# Main.net
KiCad netlist of a schematic drawn in Altium Designer
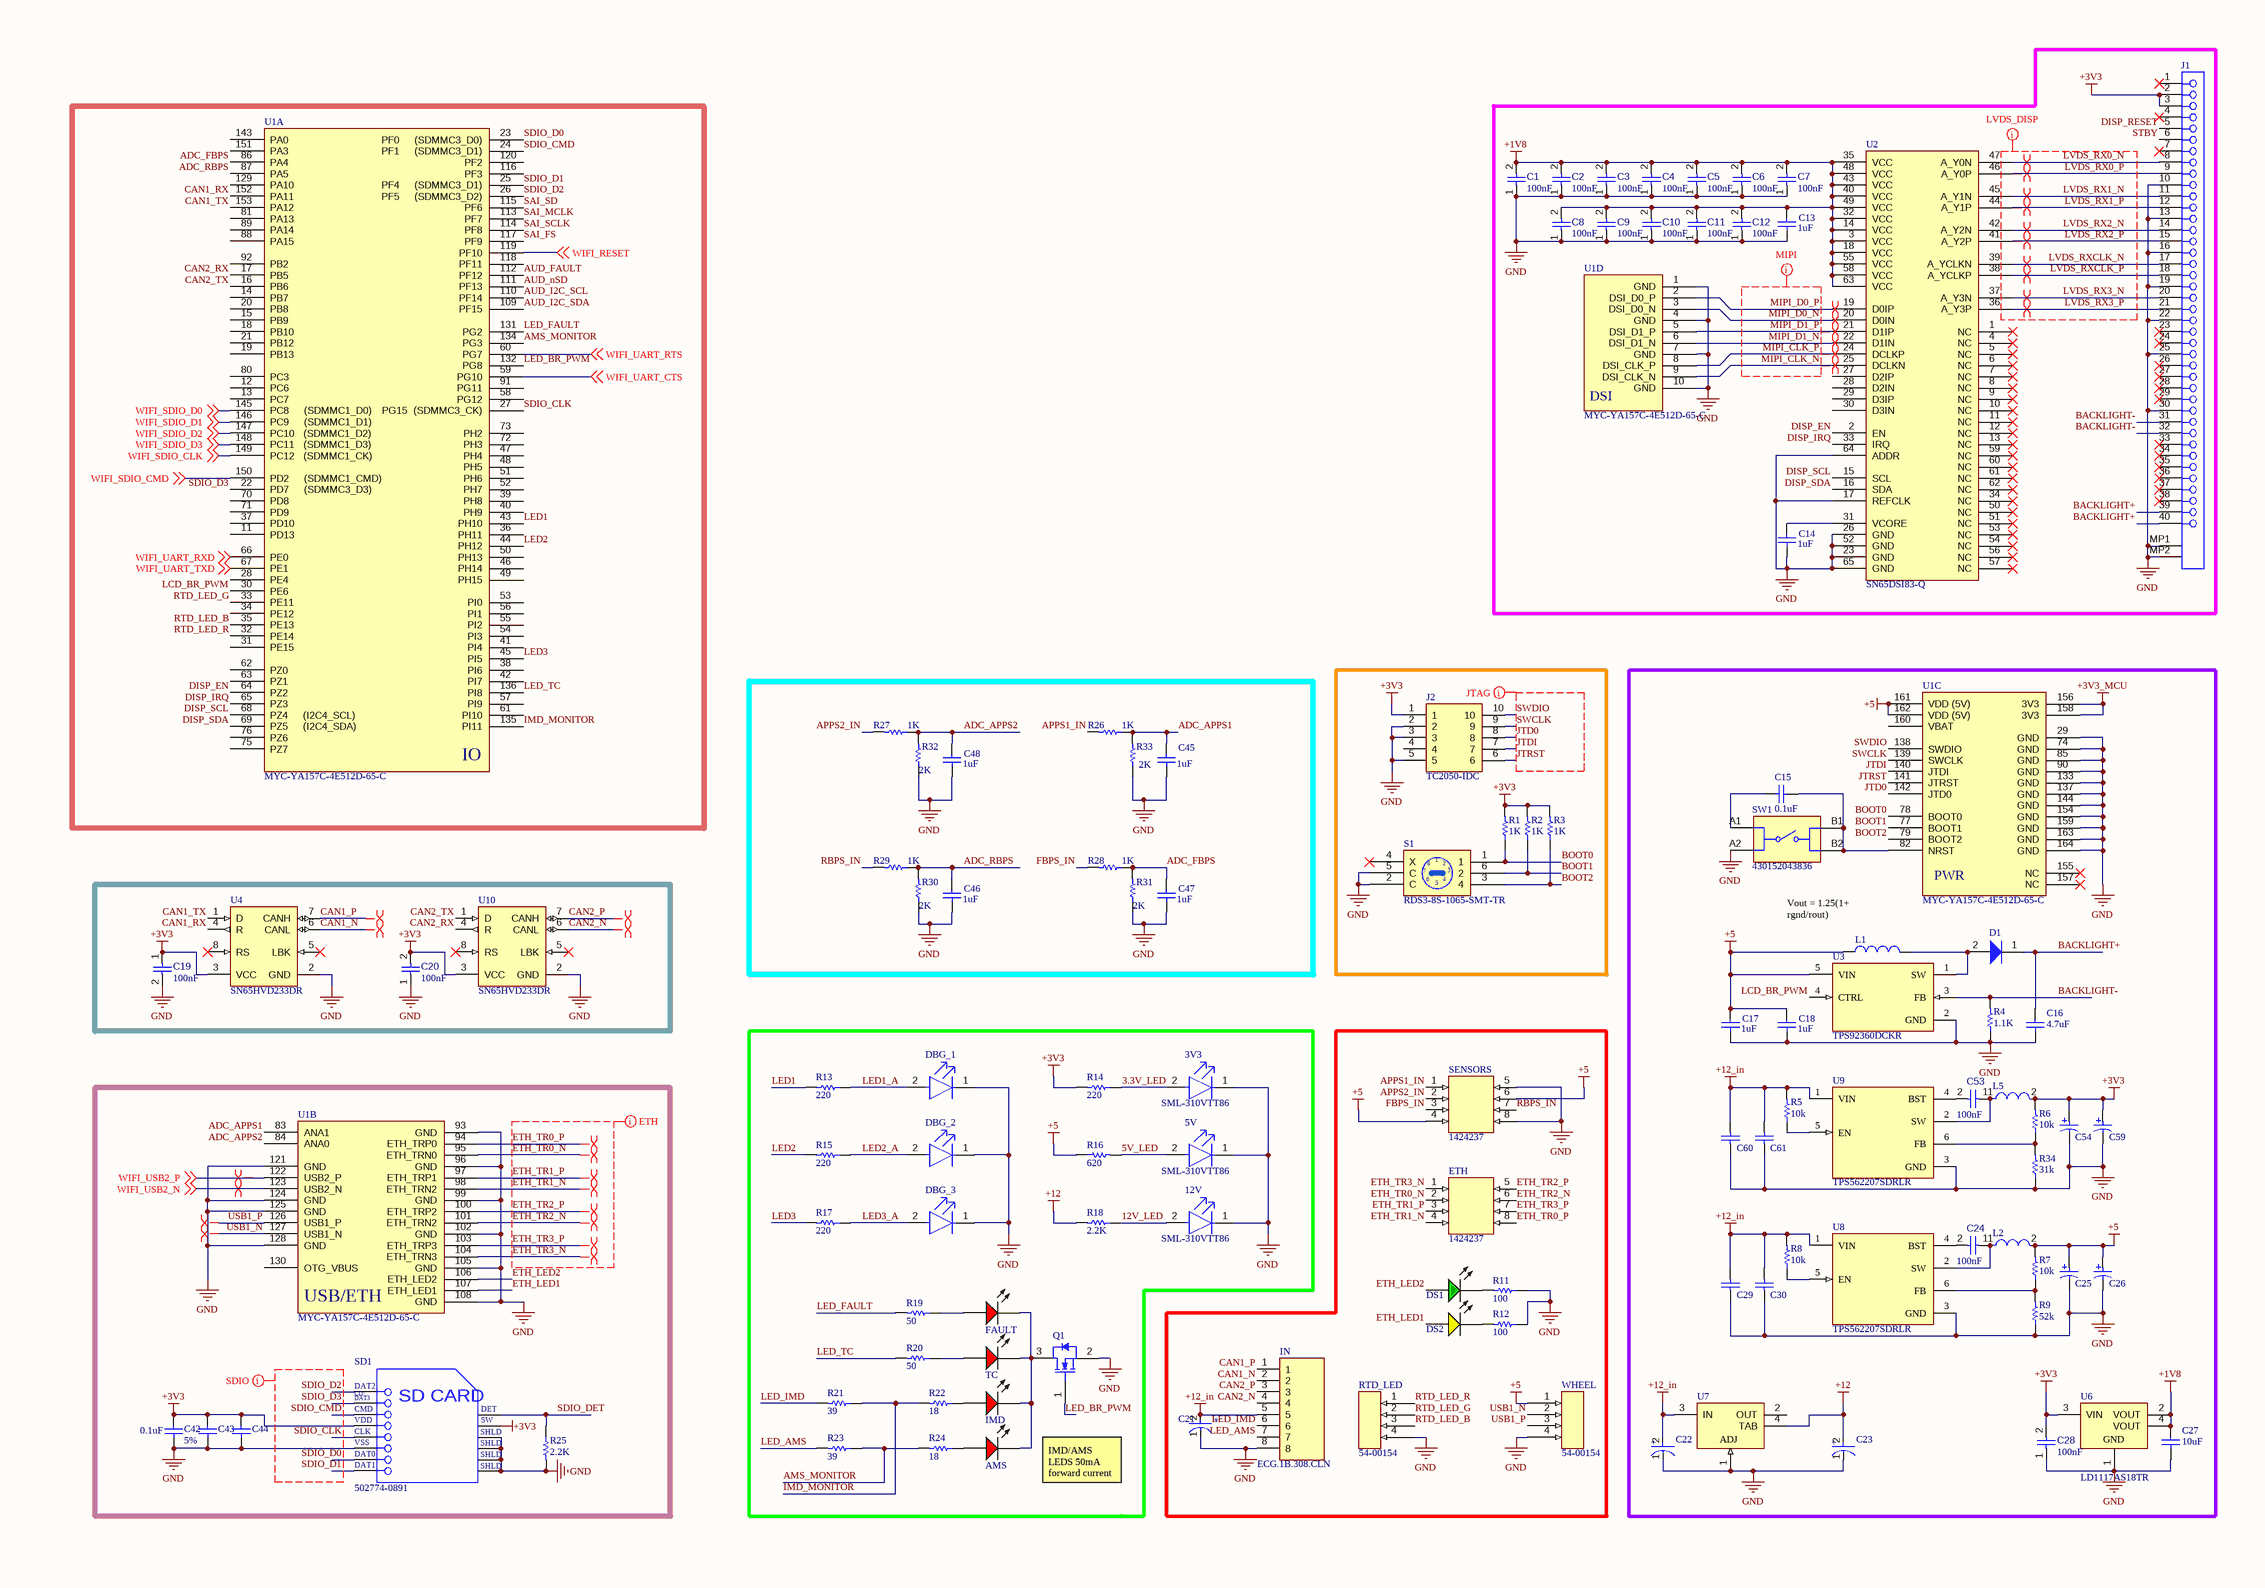
[diagram p0: Main.SchDoc]

(export (version "E")
  (design (tool "Eeschema 10.0.6"))
  (components
    (comp (ref "3V3")
      (value "SML-310VTT86")
      (footprint "FP-SML-310VTT86-MFG")
      (description "LED RED CLEAR 0603 SMD")
      (fields
        (field (name "OCTOPART") "https://octopart.com/sml-310vtt86-rohm-550741")
        (field (name "MANUFACTURER") "Rohm")
      )
      (libsource (lib "Altium Content Vault") (part "8706943c75ba83719d021d2fdc84c58"))
    )
    (comp (ref "5V")
      (value "SML-310VTT86")
      (footprint "FP-SML-310VTT86-MFG")
      (description "LED RED CLEAR 0603 SMD")
      (fields
        (field (name "OCTOPART") "https://octopart.com/sml-310vtt86-rohm-550741")
        (field (name "MANUFACTURER") "Rohm")
      )
      (libsource (lib "Altium Content Vault") (part "8706943c75ba83719d021d2fdc84c58"))
    )
    (comp (ref "12V")
      (value "SML-310VTT86")
      (footprint "FP-SML-310VTT86-MFG")
      (description "LED RED CLEAR 0603 SMD")
      (fields
        (field (name "OCTOPART") "https://octopart.com/sml-310vtt86-rohm-550741")
        (field (name "MANUFACTURER") "Rohm")
      )
      (libsource (lib "Altium Content Vault") (part "8706943c75ba83719d021d2fdc84c58"))
    )
    (comp (ref "AMS")
      (value "C503B-RAN-CY0B0AA2")
      (footprint "CREE-C503B-RAN")
      (description "Cree(R) 5-mm Red Round LED, 2.1 V, -40 to 100 degC, 2-Pin THD, RoHS, Ammo")
      (fields (field (name "MANUFACTURER") "Cree"))
      (libsource (lib "Altium Content Vault") (part "LED-RED-AK-2"))
    )
    (comp (ref "C1")
      (value "100nF")
      (footprint "CAPC0402(1005)60_L")
      (description "Chip Capacitor, 100nF +/-20%, 25V, 0402, Thickness 0.6 mm")
      (fields (field (name "TOLERANCE") "10%") (field (name "Comment") "Capacitor 100nF +/-20% 25V 0402"))
      (libsource (lib "Nicolespace") (part "CAP-NP-2"))
    )
    (comp (ref "C2")
      (value "100nF")
      (footprint "CAPC0402(1005)60_L")
      (description "Chip Capacitor, 100nF +/-20%, 25V, 0402, Thickness 0.6 mm")
      (fields (field (name "TOLERANCE") "10%") (field (name "Comment") "Capacitor 100nF +/-20% 25V 0402"))
      (libsource (lib "Nicolespace") (part "CAP-NP-2"))
    )
    (comp (ref "C3")
      (value "100nF")
      (footprint "CAPC0402(1005)60_L")
      (description "Chip Capacitor, 100nF +/-20%, 25V, 0402, Thickness 0.6 mm")
      (fields (field (name "TOLERANCE") "10%") (field (name "Comment") "Capacitor 100nF +/-20% 25V 0402"))
      (libsource (lib "Nicolespace") (part "CAP-NP-2"))
    )
    (comp (ref "C4")
      (value "100nF")
      (footprint "CAPC0402(1005)60_L")
      (description "Chip Capacitor, 100nF +/-20%, 25V, 0402, Thickness 0.6 mm")
      (fields (field (name "TOLERANCE") "10%") (field (name "Comment") "Capacitor 100nF +/-20% 25V 0402"))
      (libsource (lib "Nicolespace") (part "CAP-NP-2"))
    )
    (comp (ref "C5")
      (value "100nF")
      (footprint "CAPC0402(1005)60_L")
      (description "Chip Capacitor, 100nF +/-20%, 25V, 0402, Thickness 0.6 mm")
      (fields (field (name "TOLERANCE") "10%") (field (name "Comment") "Capacitor 100nF +/-20% 25V 0402"))
      (libsource (lib "Nicolespace") (part "CAP-NP-2"))
    )
    (comp (ref "C6")
      (value "100nF")
      (footprint "CAPC0402(1005)60_L")
      (description "Chip Capacitor, 100nF +/-20%, 25V, 0402, Thickness 0.6 mm")
      (fields (field (name "TOLERANCE") "10%") (field (name "Comment") "Capacitor 100nF +/-20% 25V 0402"))
      (libsource (lib "Nicolespace") (part "CAP-NP-2"))
    )
    (comp (ref "C7")
      (value "100nF")
      (footprint "CAPC0402(1005)60_L")
      (description "Chip Capacitor, 100nF +/-20%, 25V, 0402, Thickness 0.6 mm")
      (fields (field (name "TOLERANCE") "10%") (field (name "Comment") "Capacitor 100nF +/-20% 25V 0402"))
      (libsource (lib "Nicolespace") (part "CAP-NP-2"))
    )
    (comp (ref "C8")
      (value "100nF")
      (footprint "CAPC0402(1005)60_L")
      (description "Chip Capacitor, 100nF +/-20%, 25V, 0402, Thickness 0.6 mm")
      (fields (field (name "TOLERANCE") "10%") (field (name "Comment") "Capacitor 100nF +/-20% 25V 0402"))
      (libsource (lib "Nicolespace") (part "CAP-NP-2"))
    )
    (comp (ref "C9")
      (value "100nF")
      (footprint "CAPC0402(1005)60_L")
      (description "Chip Capacitor, 100nF +/-20%, 25V, 0402, Thickness 0.6 mm")
      (fields (field (name "TOLERANCE") "10%") (field (name "Comment") "Capacitor 100nF +/-20% 25V 0402"))
      (libsource (lib "Nicolespace") (part "CAP-NP-2"))
    )
    (comp (ref "C10")
      (value "100nF")
      (footprint "CAPC0402(1005)60_L")
      (description "Chip Capacitor, 100nF +/-20%, 25V, 0402, Thickness 0.6 mm")
      (fields (field (name "TOLERANCE") "10%") (field (name "Comment") "Capacitor 100nF +/-20% 25V 0402"))
      (libsource (lib "Nicolespace") (part "CAP-NP-2"))
    )
    (comp (ref "C11")
      (value "100nF")
      (footprint "CAPC0402(1005)60_L")
      (description "Chip Capacitor, 100nF +/-20%, 25V, 0402, Thickness 0.6 mm")
      (fields (field (name "TOLERANCE") "10%") (field (name "Comment") "Capacitor 100nF +/-20% 25V 0402"))
      (libsource (lib "Nicolespace") (part "CAP-NP-2"))
    )
    (comp (ref "C12")
      (value "100nF")
      (footprint "CAPC0402(1005)60_L")
      (description "Chip Capacitor, 100nF +/-20%, 25V, 0402, Thickness 0.6 mm")
      (fields (field (name "TOLERANCE") "10%") (field (name "Comment") "Capacitor 100nF +/-20% 25V 0402"))
      (libsource (lib "Nicolespace") (part "CAP-NP-2"))
    )
    (comp (ref "C13")
      (value "1uF")
      (footprint "1608[0603]")
      (description "Capacitor")
      (fields (field (name "Comment") "Cap"))
      (libsource (lib "WWU_RCL") (part "Capacitor"))
    )
    (comp (ref "C14")
      (value "1uF")
      (footprint "1608[0603]")
      (description "Capacitor")
      (fields (field (name "Comment") "Cap"))
      (libsource (lib "WWU_RCL") (part "Capacitor"))
    )
    (comp (ref "C15")
      (value "0.1uF")
      (footprint "1608[0603]")
      (description "Capacitor")
      (fields (field (name "Comment") "Cap"))
      (libsource (lib "WWU_RCL") (part "Capacitor"))
    )
    (comp (ref "C16")
      (value "4.7uF")
      (footprint "1608[0603]")
      (description "Capacitor")
      (fields (field (name "Comment") "Cap"))
      (libsource (lib "WWU_RCL") (part "Capacitor"))
    )
    (comp (ref "C17")
      (value "1uF")
      (footprint "1608[0603]")
      (description "Capacitor")
      (fields (field (name "Comment") "Cap"))
      (libsource (lib "WWU_RCL") (part "Capacitor"))
    )
    (comp (ref "C18")
      (value "1uF")
      (footprint "1608[0603]")
      (description "Capacitor")
      (fields (field (name "Comment") "Cap"))
      (libsource (lib "WWU_RCL") (part "Capacitor"))
    )
    (comp (ref "C19")
      (value "100nF")
      (footprint "CAPC0402(1005)60_L")
      (description "Chip Capacitor, 100nF +/-20%, 25V, 0402, Thickness 0.6 mm")
      (fields (field (name "TOLERANCE") "10%") (field (name "Comment") "Capacitor 100nF +/-20% 25V 0402"))
      (libsource (lib "Nicolespace") (part "CAP-NP-2"))
    )
    (comp (ref "C20")
      (value "100nF")
      (footprint "CAPC0402(1005)60_L")
      (description "Chip Capacitor, 100nF +/-20%, 25V, 0402, Thickness 0.6 mm")
      (fields (field (name "TOLERANCE") "10%") (field (name "Comment") "Capacitor 100nF +/-20% 25V 0402"))
      (libsource (lib "Nicolespace") (part "CAP-NP-2"))
    )
    (comp (ref "C21")
      (value "EEFCX0G181XR")
      (footprint "FP-SP-Cap-X-MFG")
      (description "Molded Aluminum Polymer Capacitor 180uF 20% 4V life 2000Hours SMD 2917")
      (libsource (lib "Altium Content Vault") (part "203bc49f2ac43e59fd269a8c329ed05"))
    )
    (comp (ref "C22")
      (value "T491B106K025AT")
      (footprint "FP-T491B106K025AT-MFG")
      (description "CAP TANT 10UF 10% 25V 1411")
      (fields (field (name "VOLTAGE") "25V") (field (name "TOLERANCE") "10%"))
      (libsource (lib "Altium Content Vault") (part "a00bbbee19879c290e62620ae7e47b1"))
    )
    (comp (ref "C23")
      (value "T491B106K025AT")
      (footprint "FP-T491B106K025AT-MFG")
      (description "CAP TANT 10UF 10% 25V 1411")
      (fields (field (name "VOLTAGE") "25V") (field (name "TOLERANCE") "10%"))
      (libsource (lib "Altium Content Vault") (part "a00bbbee19879c290e62620ae7e47b1"))
    )
    (comp (ref "C24")
      (value "100nF")
      (footprint "CAPC0402(1005)60_L")
      (description "Chip Capacitor, 100nF +/-20%, 25V, 0402, Thickness 0.6 mm")
      (fields (field (name "TOLERANCE") "10%") (field (name "Comment") "Capacitor 100nF +/-20% 25V 0402"))
      (libsource (lib "Nicolespace") (part "CAP-NP-2"))
    )
    (comp (ref "C25")
      (value "T491B226K010AT")
      (footprint "KEMT-T491-B_L")
      (description "Tantalum Capacitor, 22 uF, +/- 10%, 10 V, -55 to 125 degC, 2-Pin SMD, RoHS, Tape and Reel")
      (fields (field (name "VOLTAGE") "10VDC") (field (name "MANUFACTURER") "Kemet"))
      (libsource (lib "Altium Content Vault") (part "CAP-P-2"))
    )
    (comp (ref "C26")
      (value "T491B226K010AT")
      (footprint "KEMT-T491-B_L")
      (description "Tantalum Capacitor, 22 uF, +/- 10%, 10 V, -55 to 125 degC, 2-Pin SMD, RoHS, Tape and Reel")
      (fields (field (name "VOLTAGE") "10VDC") (field (name "MANUFACTURER") "Kemet"))
      (libsource (lib "Altium Content Vault") (part "CAP-P-2"))
    )
    (comp (ref "C27")
      (value "10uF")
      (footprint "1608[0603]")
      (description "Capacitor")
      (fields (field (name "Comment") "Cap"))
      (libsource (lib "WWU_RCL") (part "Capacitor"))
    )
    (comp (ref "C28")
      (value "100nF")
      (footprint "CAPC0402(1005)60_L")
      (description "Chip Capacitor, 100nF +/-20%, 25V, 0402, Thickness 0.6 mm")
      (fields (field (name "TOLERANCE") "10%") (field (name "Comment") "Capacitor 100nF +/-20% 25V 0402"))
      (libsource (lib "Nicolespace") (part "CAP-NP-2"))
    )
    (comp (ref "C29")
      (value "TACR106K016XTA")
      (footprint "CAPC2014X150X70NL20")
      (fields (field (name "MANUFACTURER") "AVX Interconnect / Elco"))
      (libsource (lib "Altium Content Vault") (part "CAP"))
    )
    (comp (ref "C30")
      (value "TACR106K016XTA")
      (footprint "CAPC2014X150X70NL20")
      (fields (field (name "MANUFACTURER") "AVX Interconnect / Elco"))
      (libsource (lib "Altium Content Vault") (part "CAP"))
    )
    (comp (ref "C42")
      (value "0.1uF")
      (footprint "1608[0603]")
      (description "Capacitor")
      (fields (field (name "TOLERANCE") "5%") (field (name "Comment") "Cap"))
      (libsource (lib "WWU_RCL") (part "Capacitor_0603"))
    )
    (comp (ref "C43")
      (value "Cap")
      (footprint "1608[0603]")
      (description "Capacitor")
      (fields (field (name "TOLERANCE") "5%"))
      (libsource (lib "WWU_RCL") (part "Capacitor_0603"))
    )
    (comp (ref "C44")
      (value "Cap")
      (footprint "1608[0603]")
      (description "Capacitor")
      (fields (field (name "TOLERANCE") "5%"))
      (libsource (lib "WWU_RCL") (part "Capacitor_0603"))
    )
    (comp (ref "C45")
      (value "1uF")
      (footprint "1608[0603]")
      (description "Capacitor")
      (fields (field (name "Comment") "Cap"))
      (libsource (lib "WWU_RCL") (part "Capacitor"))
    )
    (comp (ref "C46")
      (value "1uF")
      (footprint "1608[0603]")
      (description "Capacitor")
      (fields (field (name "Comment") "Cap"))
      (libsource (lib "WWU_RCL") (part "Capacitor"))
    )
    (comp (ref "C47")
      (value "1uF")
      (footprint "1608[0603]")
      (description "Capacitor")
      (fields (field (name "Comment") "Cap"))
      (libsource (lib "WWU_RCL") (part "Capacitor"))
    )
    (comp (ref "C48")
      (value "1uF")
      (footprint "1608[0603]")
      (description "Capacitor")
      (fields (field (name "Comment") "Cap"))
      (libsource (lib "WWU_RCL") (part "Capacitor"))
    )
    (comp (ref "C53")
      (value "100nF")
      (footprint "CAPC0402(1005)60_L")
      (description "Chip Capacitor, 100nF +/-20%, 25V, 0402, Thickness 0.6 mm")
      (fields (field (name "TOLERANCE") "10%") (field (name "Comment") "Capacitor 100nF +/-20% 25V 0402"))
      (libsource (lib "Nicolespace") (part "CAP-NP-2"))
    )
    (comp (ref "C54")
      (value "T491B226K010AT")
      (footprint "KEMT-T491-B_L")
      (description "Tantalum Capacitor, 22 uF, +/- 10%, 10 V, -55 to 125 degC, 2-Pin SMD, RoHS, Tape and Reel")
      (fields (field (name "VOLTAGE") "10VDC") (field (name "MANUFACTURER") "Kemet"))
      (libsource (lib "Altium Content Vault") (part "CAP-P-2"))
    )
    (comp (ref "C59")
      (value "T491B226K010AT")
      (footprint "KEMT-T491-B_L")
      (description "Tantalum Capacitor, 22 uF, +/- 10%, 10 V, -55 to 125 degC, 2-Pin SMD, RoHS, Tape and Reel")
      (fields (field (name "VOLTAGE") "10VDC") (field (name "MANUFACTURER") "Kemet"))
      (libsource (lib "Altium Content Vault") (part "CAP-P-2"))
    )
    (comp (ref "C60")
      (value "TACR106K016XTA")
      (footprint "CAPC2014X150X70NL20")
      (fields (field (name "MANUFACTURER") "AVX Interconnect / Elco"))
      (libsource (lib "Altium Content Vault") (part "CAP"))
    )
    (comp (ref "C61")
      (value "TACR106K016XTA")
      (footprint "CAPC2014X150X70NL20")
      (fields (field (name "MANUFACTURER") "AVX Interconnect / Elco"))
      (libsource (lib "Altium Content Vault") (part "CAP"))
    )
    (comp (ref "D1")
      (value "NSR0240HT1G")
      (footprint "ONSC-SOD-323-2-477-02_V")
      (description "Schottky Barrier Diode, 2-Pin SOD-323, Pb-Free, Tape and Reel")
      (fields (field (name "MANUFACTURER") "On Semiconductor"))
      (libsource (lib "Altium Content Vault") (part "ONSC-D-K1A2-2"))
    )
    (comp (ref "DBG_1")
      (value "SML-310VTT86")
      (footprint "FP-SML-310VTT86-MFG")
      (description "LED RED CLEAR 0603 SMD")
      (fields
        (field (name "OCTOPART") "https://octopart.com/sml-310vtt86-rohm-550741")
        (field (name "MANUFACTURER") "Rohm")
      )
      (libsource (lib "Altium Content Vault") (part "8706943c75ba83719d021d2fdc84c58"))
    )
    (comp (ref "DBG_2")
      (value "SML-310VTT86")
      (footprint "FP-SML-310VTT86-MFG")
      (description "LED RED CLEAR 0603 SMD")
      (fields
        (field (name "OCTOPART") "https://octopart.com/sml-310vtt86-rohm-550741")
        (field (name "MANUFACTURER") "Rohm")
      )
      (libsource (lib "Altium Content Vault") (part "8706943c75ba83719d021d2fdc84c58"))
    )
    (comp (ref "DBG_3")
      (value "SML-310VTT86")
      (footprint "FP-SML-310VTT86-MFG")
      (description "LED RED CLEAR 0603 SMD")
      (fields
        (field (name "OCTOPART") "https://octopart.com/sml-310vtt86-rohm-550741")
        (field (name "MANUFACTURER") "Rohm")
      )
      (libsource (lib "Altium Content Vault") (part "8706943c75ba83719d021d2fdc84c58"))
    )
    (comp (ref "DS1")
      (value "HSMG-C190")
      (footprint "AVAG-HSMX-C190_V")
      (description "Chip LED, Green, 2.2 V, -40 to 85 degC, 2-Pin SMD, RoHS, Tape and Reel")
      (libsource (lib "Altium Content Vault") (part "LED-GREEN-AK-2"))
    )
    (comp (ref "DS2")
      (value "HSMY-C190")
      (footprint "AVAG-HSMX-C190_V")
      (description "LED Uni-Color Yellow, 65 mW, 20 mA, -40 to 85 degC, 2-Pin SMD, RoHS, Tape and Reel")
      (fields (field (name "TOLERANCE") "1%"))
      (libsource (lib "Altium Content Vault") (part "LED-YELLOW-AK-2"))
    )
    (comp (ref "ETH")
      (value "1424237")
      (footprint "1424237")
      (description "Circular Connector")
      (libsource (lib "Nicolespace") (part "1424237"))
    )
    (comp (ref "FAULT")
      (value "C503B-RAN-CY0B0AA2")
      (footprint "CREE-C503B-RAN")
      (description "Cree(R) 5-mm Red Round LED, 2.1 V, -40 to 100 degC, 2-Pin THD, RoHS, Ammo")
      (fields (field (name "MANUFACTURER") "Cree"))
      (libsource (lib "Altium Content Vault") (part "LED-RED-AK-2"))
    )
    (comp (ref "IMD")
      (value "C503B-RAN-CY0B0AA2")
      (footprint "CREE-C503B-RAN")
      (description "Cree(R) 5-mm Red Round LED, 2.1 V, -40 to 100 degC, 2-Pin THD, RoHS, Ammo")
      (fields (field (name "MANUFACTURER") "Cree"))
      (libsource (lib "Altium Content Vault") (part "LED-RED-AK-2"))
    )
    (comp (ref "IN")
      (value "ECG.1B.308.CLN")
      (footprint "LEMO_ECG.1B.308.CLN")
      (description "Conn Circular F 8 POS Solder ST Thru-Hole 8 Terminal 1 Port")
      (libsource (lib "Nicolespace") (part "ECG.1B.308.CLN"))
    )
    (comp (ref "J1")
      (value "54104-4031")
      (footprint "MOLX-54104-4031")
      (fields (field (name "MANUFACTURER") "Molex"))
      (libsource (lib "Altium Content Vault") (part "MOLX-54104-4031"))
    )
    (comp (ref "J2")
      (value "TC2050-IDC")
      (footprint "WWU_CONN:TC2050-IDC")
      (description "Connector")
      (libsource (lib "WWU_CONN") (part "TC2050-IDC"))
    )
    (comp (ref "L1")
      (value "LPS4018-472MR")
      (footprint "LPS4018-472MR-Footprint-1")
      (libsource (lib "Nicolespace") (part "IND-2"))
    )
    (comp (ref "L2")
      (value "IHLP2525AHER4R7M01")
      (footprint "FP-IHLP-2525AH-FP_2_413x3-MFG")
      (description "Commercial Inductors, High Saturation Series 4.7uH 3A 78mΩ 20%")
      (fields (field (name "TOLERANCE") "20%"))
      (libsource (lib "Altium Content Vault") (part "725321dda6339637d4d059423bc1c3c"))
    )
    (comp (ref "L5")
      (value "IHLP2525AHER4R7M01")
      (footprint "FP-IHLP-2525AH-FP_2_413x3-MFG")
      (description "Commercial Inductors, High Saturation Series 4.7uH 3A 78mΩ 20%")
      (fields (field (name "TOLERANCE") "20%"))
      (libsource (lib "Altium Content Vault") (part "725321dda6339637d4d059423bc1c3c"))
    )
    (comp (ref "Q1")
      (value "NTR4170NT1G")
      (footprint "ONSC-SOT-23-3-318-08_V")
      (description "Power MOSFET, 30 V, 3.1 A, Single N-Channe, 3-Pin SOT-23, Pb-Free, Tape and Reel")
      (fields (field (name "MANUFACTURER") "On Semiconductor"))
      (libsource (lib "Altium Content Vault") (part "ONSC-NMOS-G1S2D3-3"))
    )
    (comp (ref "R1")
      (value "1K")
      (footprint "RESC1609X50X30NL8T20")
      (description "Chip Resistor, 10 KOhm, +/- 1%, 100 mW, -55 to 155 degC, 0603 (1608 Metric), RoHS, Tape and Reel")
      (fields (field (name "MANUFACTURER") "Vishay Semiconductor"))
      (libsource (lib "Altium Content Vault") (part "RES-2"))
    )
    (comp (ref "R2")
      (value "1K")
      (footprint "RESC1609X50X30NL8T20")
      (description "Chip Resistor, 10 KOhm, +/- 1%, 100 mW, -55 to 155 degC, 0603 (1608 Metric), RoHS, Tape and Reel")
      (fields (field (name "MANUFACTURER") "Vishay Semiconductor"))
      (libsource (lib "Altium Content Vault") (part "RES-2"))
    )
    (comp (ref "R3")
      (value "1K")
      (footprint "RESC1609X50X30NL8T20")
      (description "Chip Resistor, 10 KOhm, +/- 1%, 100 mW, -55 to 155 degC, 0603 (1608 Metric), RoHS, Tape and Reel")
      (fields (field (name "MANUFACTURER") "Vishay Semiconductor"))
      (libsource (lib "Altium Content Vault") (part "RES-2"))
    )
    (comp (ref "R4")
      (value "1.1K")
      (footprint "RESC1609X50X30NL8T20")
      (description "Chip Resistor, 10 KOhm, +/- 1%, 100 mW, -55 to 155 degC, 0603 (1608 Metric), RoHS, Tape and Reel")
      (fields (field (name "MANUFACTURER") "Vishay Semiconductor"))
      (libsource (lib "Altium Content Vault") (part "RES-2"))
    )
    (comp (ref "R5")
      (value "10k")
      (footprint "RESC1609X50X30NL8T20")
      (description "Chip Resistor, 10 KOhm, +/- 1%, 100 mW, -55 to 155 degC, 0603 (1608 Metric), RoHS, Tape and Reel")
      (fields (field (name "MANUFACTURER") "Vishay Semiconductor"))
      (libsource (lib "Altium Content Vault") (part "RES-2"))
    )
    (comp (ref "R6")
      (value "10k")
      (footprint "RESC1609X50X30NL8T20")
      (description "Chip Resistor, 10 KOhm, +/- 1%, 100 mW, -55 to 155 degC, 0603 (1608 Metric), RoHS, Tape and Reel")
      (fields (field (name "MANUFACTURER") "Vishay Semiconductor"))
      (libsource (lib "Altium Content Vault") (part "RES-2"))
    )
    (comp (ref "R7")
      (value "10k")
      (footprint "RESC1609X50X30NL8T20")
      (description "Chip Resistor, 10 KOhm, +/- 1%, 100 mW, -55 to 155 degC, 0603 (1608 Metric), RoHS, Tape and Reel")
      (fields (field (name "MANUFACTURER") "Vishay Semiconductor"))
      (libsource (lib "Altium Content Vault") (part "RES-2"))
    )
    (comp (ref "R8")
      (value "10k")
      (footprint "RESC1609X50X30NL8T20")
      (description "Chip Resistor, 10 KOhm, +/- 1%, 100 mW, -55 to 155 degC, 0603 (1608 Metric), RoHS, Tape and Reel")
      (fields (field (name "MANUFACTURER") "Vishay Semiconductor"))
      (libsource (lib "Altium Content Vault") (part "RES-2"))
    )
    (comp (ref "R9")
      (value "52k")
      (footprint "RESC1609X50X30NL8T20")
      (description "Chip Resistor, 10 KOhm, +/- 1%, 100 mW, -55 to 155 degC, 0603 (1608 Metric), RoHS, Tape and Reel")
      (fields (field (name "MANUFACTURER") "Vishay Semiconductor"))
      (libsource (lib "Altium Content Vault") (part "RES-2"))
    )
    (comp (ref "R11")
      (value "100")
      (footprint "RESC1609X50X30NL8T20")
      (description "Chip Resistor, 10 KOhm, +/- 1%, 100 mW, -55 to 155 degC, 0603 (1608 Metric), RoHS, Tape and Reel")
      (fields (field (name "MANUFACTURER") "Vishay Semiconductor"))
      (libsource (lib "Altium Content Vault") (part "RES-2"))
    )
    (comp (ref "R12")
      (value "100")
      (footprint "RESC1609X50X30NL8T20")
      (description "Chip Resistor, 10 KOhm, +/- 1%, 100 mW, -55 to 155 degC, 0603 (1608 Metric), RoHS, Tape and Reel")
      (fields (field (name "MANUFACTURER") "Vishay Semiconductor"))
      (libsource (lib "Altium Content Vault") (part "RES-2"))
    )
    (comp (ref "R13")
      (value "220")
      (footprint "RESC1609X50X30NL8T20")
      (description "Chip Resistor, 10 KOhm, +/- 1%, 100 mW, -55 to 155 degC, 0603 (1608 Metric), RoHS, Tape and Reel")
      (fields (field (name "MANUFACTURER") "Vishay Semiconductor"))
      (libsource (lib "Altium Content Vault") (part "RES-2"))
    )
    (comp (ref "R14")
      (value "220")
      (footprint "RESC1609X50X30NL8T20")
      (description "Chip Resistor, 10 KOhm, +/- 1%, 100 mW, -55 to 155 degC, 0603 (1608 Metric), RoHS, Tape and Reel")
      (fields (field (name "MANUFACTURER") "Vishay Semiconductor"))
      (libsource (lib "Altium Content Vault") (part "RES-2"))
    )
    (comp (ref "R15")
      (value "220")
      (footprint "RESC1609X50X30NL8T20")
      (description "Chip Resistor, 10 KOhm, +/- 1%, 100 mW, -55 to 155 degC, 0603 (1608 Metric), RoHS, Tape and Reel")
      (fields (field (name "MANUFACTURER") "Vishay Semiconductor"))
      (libsource (lib "Altium Content Vault") (part "RES-2"))
    )
    (comp (ref "R16")
      (value "620")
      (footprint "RESC1609X50X30NL8T20")
      (description "Chip Resistor, 10 KOhm, +/- 1%, 100 mW, -55 to 155 degC, 0603 (1608 Metric), RoHS, Tape and Reel")
      (fields (field (name "MANUFACTURER") "Vishay Semiconductor"))
      (libsource (lib "Altium Content Vault") (part "RES-2"))
    )
    (comp (ref "R17")
      (value "220")
      (footprint "RESC1609X50X30NL8T20")
      (description "Chip Resistor, 10 KOhm, +/- 1%, 100 mW, -55 to 155 degC, 0603 (1608 Metric), RoHS, Tape and Reel")
      (fields (field (name "MANUFACTURER") "Vishay Semiconductor"))
      (libsource (lib "Altium Content Vault") (part "RES-2"))
    )
    (comp (ref "R18")
      (value "2.2K")
      (footprint "RESC1609X50X30NL8T20")
      (description "Chip Resistor, 10 KOhm, +/- 1%, 100 mW, -55 to 155 degC, 0603 (1608 Metric), RoHS, Tape and Reel")
      (fields (field (name "MANUFACTURER") "Vishay Semiconductor"))
      (libsource (lib "Altium Content Vault") (part "RES-2"))
    )
    (comp (ref "R19")
      (value "50")
      (footprint "RESC1609X50X30NL8T20")
      (description "Chip Resistor, 10 KOhm, +/- 1%, 100 mW, -55 to 155 degC, 0603 (1608 Metric), RoHS, Tape and Reel")
      (fields (field (name "MANUFACTURER") "Vishay Semiconductor"))
      (libsource (lib "Altium Content Vault") (part "RES-2"))
    )
    (comp (ref "R20")
      (value "50")
      (footprint "RESC1609X50X30NL8T20")
      (description "Chip Resistor, 10 KOhm, +/- 1%, 100 mW, -55 to 155 degC, 0603 (1608 Metric), RoHS, Tape and Reel")
      (fields (field (name "MANUFACTURER") "Vishay Semiconductor"))
      (libsource (lib "Altium Content Vault") (part "RES-2"))
    )
    (comp (ref "R21")
      (value "39")
      (footprint "RESC1609X50X30NL8T20")
      (description "Chip Resistor, 10 KOhm, +/- 1%, 100 mW, -55 to 155 degC, 0603 (1608 Metric), RoHS, Tape and Reel")
      (fields (field (name "MANUFACTURER") "Vishay Semiconductor"))
      (libsource (lib "Altium Content Vault") (part "RES-2"))
    )
    (comp (ref "R22")
      (value "18")
      (footprint "RESC1609X50X30NL8T20")
      (description "Chip Resistor, 10 KOhm, +/- 1%, 100 mW, -55 to 155 degC, 0603 (1608 Metric), RoHS, Tape and Reel")
      (fields (field (name "MANUFACTURER") "Vishay Semiconductor"))
      (libsource (lib "Altium Content Vault") (part "RES-2"))
    )
    (comp (ref "R23")
      (value "39")
      (footprint "RESC1609X50X30NL8T20")
      (description "Chip Resistor, 10 KOhm, +/- 1%, 100 mW, -55 to 155 degC, 0603 (1608 Metric), RoHS, Tape and Reel")
      (fields (field (name "MANUFACTURER") "Vishay Semiconductor"))
      (libsource (lib "Altium Content Vault") (part "RES-2"))
    )
    (comp (ref "R24")
      (value "18")
      (footprint "RESC1609X50X30NL8T20")
      (description "Chip Resistor, 10 KOhm, +/- 1%, 100 mW, -55 to 155 degC, 0603 (1608 Metric), RoHS, Tape and Reel")
      (fields (field (name "MANUFACTURER") "Vishay Semiconductor"))
      (libsource (lib "Altium Content Vault") (part "RES-2"))
    )
    (comp (ref "R25")
      (value "2.2K")
      (footprint "RESC1609X50X30NL8T20")
      (description "Chip Resistor, 10 KOhm, +/- 1%, 100 mW, -55 to 155 degC, 0603 (1608 Metric), RoHS, Tape and Reel")
      (fields (field (name "MANUFACTURER") "Vishay Semiconductor"))
      (libsource (lib "Altium Content Vault") (part "RES-2"))
    )
    (comp (ref "R26")
      (value "1K")
      (footprint "RESC1609X50X30NL8T20")
      (description "Chip Resistor, 10 KOhm, +/- 1%, 100 mW, -55 to 155 degC, 0603 (1608 Metric), RoHS, Tape and Reel")
      (fields (field (name "MANUFACTURER") "Vishay Semiconductor"))
      (libsource (lib "Altium Content Vault") (part "RES-2"))
    )
    (comp (ref "R27")
      (value "1K")
      (footprint "RESC1609X50X30NL8T20")
      (description "Chip Resistor, 10 KOhm, +/- 1%, 100 mW, -55 to 155 degC, 0603 (1608 Metric), RoHS, Tape and Reel")
      (fields (field (name "MANUFACTURER") "Vishay Semiconductor"))
      (libsource (lib "Altium Content Vault") (part "RES-2"))
    )
    (comp (ref "R28")
      (value "1K")
      (footprint "RESC1609X50X30NL8T20")
      (description "Chip Resistor, 10 KOhm, +/- 1%, 100 mW, -55 to 155 degC, 0603 (1608 Metric), RoHS, Tape and Reel")
      (fields (field (name "MANUFACTURER") "Vishay Semiconductor"))
      (libsource (lib "Altium Content Vault") (part "RES-2"))
    )
    (comp (ref "R29")
      (value "1K")
      (footprint "RESC1609X50X30NL8T20")
      (description "Chip Resistor, 10 KOhm, +/- 1%, 100 mW, -55 to 155 degC, 0603 (1608 Metric), RoHS, Tape and Reel")
      (fields (field (name "MANUFACTURER") "Vishay Semiconductor"))
      (libsource (lib "Altium Content Vault") (part "RES-2"))
    )
    (comp (ref "R30")
      (value "2K")
      (footprint "RESC1609X50X30NL8T20")
      (description "Chip Resistor, 10 KOhm, +/- 1%, 100 mW, -55 to 155 degC, 0603 (1608 Metric), RoHS, Tape and Reel")
      (fields (field (name "MANUFACTURER") "Vishay Semiconductor"))
      (libsource (lib "Altium Content Vault") (part "RES-2"))
    )
    (comp (ref "R31")
      (value "2K")
      (footprint "RESC1609X50X30NL8T20")
      (description "Chip Resistor, 10 KOhm, +/- 1%, 100 mW, -55 to 155 degC, 0603 (1608 Metric), RoHS, Tape and Reel")
      (fields (field (name "MANUFACTURER") "Vishay Semiconductor"))
      (libsource (lib "Altium Content Vault") (part "RES-2"))
    )
    (comp (ref "R32")
      (value "2K")
      (footprint "RESC1609X50X30NL8T20")
      (description "Chip Resistor, 10 KOhm, +/- 1%, 100 mW, -55 to 155 degC, 0603 (1608 Metric), RoHS, Tape and Reel")
      (fields (field (name "MANUFACTURER") "Vishay Semiconductor"))
      (libsource (lib "Altium Content Vault") (part "RES-2"))
    )
    (comp (ref "R33")
      (value "2K")
      (footprint "RESC1609X50X30NL8T20")
      (description "Chip Resistor, 10 KOhm, +/- 1%, 100 mW, -55 to 155 degC, 0603 (1608 Metric), RoHS, Tape and Reel")
      (fields (field (name "MANUFACTURER") "Vishay Semiconductor"))
      (libsource (lib "Altium Content Vault") (part "RES-2"))
    )
    (comp (ref "R34")
      (value "31k")
      (footprint "RESC1609X50X30NL8T20")
      (description "Chip Resistor, 10 KOhm, +/- 1%, 100 mW, -55 to 155 degC, 0603 (1608 Metric), RoHS, Tape and Reel")
      (fields (field (name "MANUFACTURER") "Vishay Semiconductor"))
      (libsource (lib "Altium Content Vault") (part "RES-2"))
    )
    (comp (ref "RTD_LED")
      (value "54-00154")
      (footprint "54-00154-Footprint-1")
      (description "Conn Rcpt Fmale Pnl Mnt 4POS")
      (libsource (lib "Nicolespace") (part "54-00154"))
    )
    (comp (ref "S1")
      (value "RDS3-8S-1065-SMT-TR")
      (footprint "RDS3-8S-1065-SMT-TR-Footprint-1")
      (description "switch")
      (libsource (lib "Nicolespace") (part "RDS3-8S-1065"))
    )
    (comp (ref "SD1")
      (value "502774-0891")
      (footprint "MOLX-502774-0891_V")
      (description "Micro SD Memory Card Connector, 0.5 A, 10 V (DC), -25 to 85 degC, 8-Pin SMT, RoHS, Tape and Reel")
      (fields (field (name "MANUFACTURER") "Molex"))
      (libsource (lib "Altium Content Vault") (part "CN-SD-8-2SW-4S_B"))
    )
    (comp (ref "SENSORS")
      (value "1424237")
      (footprint "1424237")
      (description "Circular Connector")
      (libsource (lib "Nicolespace") (part "1424237"))
    )
    (comp (ref "SW1")
      (value "430152043836")
      (footprint "WS-TASV_L6W6H4.3_4301x20438x6")
      (libsource (lib "Altium Content Vault") (part "SPST-NO_4P"))
    )
    (comp (ref "TC")
      (value "C503B-RAN-CY0B0AA2")
      (footprint "CREE-C503B-RAN")
      (description "Cree(R) 5-mm Red Round LED, 2.1 V, -40 to 100 degC, 2-Pin THD, RoHS, Ammo")
      (fields (field (name "MANUFACTURER") "Cree"))
      (libsource (lib "Altium Content Vault") (part "LED-RED-AK-2"))
    )
    (comp (ref "U1")
      (value "MYC-YA157C-4E512D-65-C")
      (footprint "New footprint 1")
      (description "Thing from china")
      (libsource (lib "Nicolespace") (part "MYC_YA157C"))
    )
    (comp (ref "U2")
      (value "SN65DSI83-Q")
      (footprint "TSQFP50P1200X1200X120_HS-65N")
      (description "MIPI to LVDS converter")
      (libsource (lib "Nicolespace") (part "SN65DSI83-Q-Symbol-1"))
    )
    (comp (ref "U3")
      (value "TPS92360DCKR")
      (footprint "FP-DCK0005A-IPC_C")
      (description "38-V 1.2-A single channel LED backlight driver 5-SC70 -40 to 85")
      (libsource (lib "Altium Content Vault") (part "12534fec95d33ffe398d5dc1ac97ce6"))
    )
    (comp (ref "U4")
      (value "SN65HVD233DR")
      (footprint "D0008A_M")
      (fields (field (name "MANUFACTURER") "Texas Instruments"))
      (libsource (lib "Altium Content Vault") (part "TI-SN65HVD233-SOIC_D-8"))
    )
    (comp (ref "U6")
      (value "LD1117AS18TR")
      (footprint "SOT-223_L")
      (description "1A, Low Drop Positive Voltage Regulator, 1.8V, 4-Pin SOT-223, Tape and Reel")
      (libsource (lib "Altium Content Vault") (part "PM-REG-LD1117-SOT4"))
    )
    (comp (ref "U7")
      (value "LM1085IS-ADJ/NOPB")
      (footprint "KTT0003B_M")
      (description "3A Low Dropout Positive Regulators, 3-pin TO-263, Pb-Free")
      (fields (field (name "MANUFACTURER") "Texas Instruments"))
      (libsource (lib "Altium Content Vault") (part "PM-REG-LM1086ADJ-SOT4"))
    )
    (comp (ref "U8")
      (value "TPS562207SDRLR")
      (footprint "FP-DRL0006A-MFG")
      (description "4.3-V TO 17-V INPUT, 2-A FCCM MO")
      (libsource (lib "Altium Content Vault") (part "20a8199d08744f150f5e4322a25df50"))
    )
    (comp (ref "U9")
      (value "TPS562207SDRLR")
      (footprint "FP-DRL0006A-MFG")
      (description "4.3-V TO 17-V INPUT, 2-A FCCM MO")
      (libsource (lib "Altium Content Vault") (part "20a8199d08744f150f5e4322a25df50"))
    )
    (comp (ref "U10")
      (value "SN65HVD233DR")
      (footprint "D0008A_M")
      (fields (field (name "MANUFACTURER") "Texas Instruments"))
      (libsource (lib "Altium Content Vault") (part "TI-SN65HVD233-SOIC_D-8"))
    )
    (comp (ref "WHEEL")
      (value "54-00154")
      (footprint "54-00154-Footprint-1")
      (description "Conn Rcpt Fmale Pnl Mnt 4POS")
      (libsource (lib "") (part "54-00154_1"))
    )
  )
  (nets
    (net (code "1") (name "+1V8") (class "Default")
      (node (ref "C1") (pin "2") (pinfunction "2_2") (pintype "passive"))
      (node (ref "C10") (pin "2") (pinfunction "2_2") (pintype "passive"))
      (node (ref "C11") (pin "2") (pinfunction "2_2") (pintype "passive"))
      (node (ref "C12") (pin "2") (pinfunction "2_2") (pintype "passive"))
      (node (ref "C13") (pin "2") (pintype "passive"))
      (node (ref "C2") (pin "2") (pinfunction "2_2") (pintype "passive"))
      (node (ref "C27") (pin "2") (pintype "passive"))
      (node (ref "C3") (pin "2") (pinfunction "2_2") (pintype "passive"))
      (node (ref "C4") (pin "2") (pinfunction "2_2") (pintype "passive"))
      (node (ref "C5") (pin "2") (pinfunction "2_2") (pintype "passive"))
      (node (ref "C6") (pin "2") (pinfunction "2_2") (pintype "passive"))
      (node (ref "C7") (pin "2") (pinfunction "2_2") (pintype "passive"))
      (node (ref "C8") (pin "2") (pinfunction "2_2") (pintype "passive"))
      (node (ref "C9") (pin "2") (pinfunction "2_2") (pintype "passive"))
      (node (ref "U2") (pin "14") (pinfunction "VCC_14") (pintype "passive"))
      (node (ref "U2") (pin "18") (pinfunction "VCC_18") (pintype "passive"))
      (node (ref "U2") (pin "3") (pinfunction "VCC_3") (pintype "passive"))
      (node (ref "U2") (pin "32") (pinfunction "VCC_32") (pintype "passive"))
      (node (ref "U2") (pin "35") (pinfunction "VCC_35") (pintype "passive"))
      (node (ref "U2") (pin "40") (pinfunction "VCC_40") (pintype "passive"))
      (node (ref "U2") (pin "43") (pinfunction "VCC_43") (pintype "passive"))
      (node (ref "U2") (pin "48") (pinfunction "VCC_48") (pintype "passive"))
      (node (ref "U2") (pin "49") (pinfunction "VCC_49") (pintype "passive"))
      (node (ref "U2") (pin "55") (pinfunction "VCC_55") (pintype "passive"))
      (node (ref "U2") (pin "58") (pinfunction "VCC_58") (pintype "passive"))
      (node (ref "U2") (pin "63") (pinfunction "VCC_63") (pintype "passive"))
      (node (ref "U6") (pin "2") (pinfunction "VOUT_2") (pintype "power_in"))
      (node (ref "U6") (pin "4") (pinfunction "VOUT_4") (pintype "power_in"))
    )
    (net (code "2") (name "+3V3") (class "Default")
      (node (ref "C19") (pin "1") (pinfunction "1_1") (pintype "passive"))
      (node (ref "C20") (pin "2") (pinfunction "2_2") (pintype "passive"))
      (node (ref "C28") (pin "2") (pinfunction "2_2") (pintype "passive"))
      (node (ref "C42") (pin "2") (pintype "passive"))
      (node (ref "C43") (pin "2") (pintype "passive"))
      (node (ref "C44") (pin "2") (pintype "passive"))
      (node (ref "C54") (pin "1") (pinfunction "1_1") (pintype "passive"))
      (node (ref "C59") (pin "1") (pinfunction "1_1") (pintype "passive"))
      (node (ref "J1") (pin "2") (pinfunction "2_2") (pintype "passive"))
      (node (ref "J1") (pin "3") (pinfunction "3_3") (pintype "passive"))
      (node (ref "J2") (pin "1") (pinfunction "1_1") (pintype "passive"))
      (node (ref "L5") (pin "2") (pinfunction "2_2") (pintype "passive"))
      (node (ref "R1") (pin "2") (pinfunction "2_2") (pintype "passive"))
      (node (ref "R14") (pin "2") (pinfunction "2_2") (pintype "passive"))
      (node (ref "R2") (pin "2") (pinfunction "2_2") (pintype "passive"))
      (node (ref "R3") (pin "2") (pinfunction "2_2") (pintype "passive"))
      (node (ref "R6") (pin "2") (pinfunction "2_2") (pintype "passive"))
      (node (ref "SD1") (pin "10") (pinfunction "SWITCH_10") (pintype "passive"))
      (node (ref "SD1") (pin "4") (pinfunction "VDD_4") (pintype "passive"))
      (node (ref "U10") (pin "3") (pinfunction "VCC_3") (pintype "power_in"))
      (node (ref "U4") (pin "3") (pinfunction "VCC_3") (pintype "power_in"))
      (node (ref "U6") (pin "3") (pinfunction "VIN_3") (pintype "power_in"))
    )
    (net (code "3") (name "+3V3_MCU") (class "Default")
      (node (ref "U1") (pin "156") (pinfunction "3V3_156") (pintype "passive"))
      (node (ref "U1") (pin "158") (pinfunction "3V3_158") (pintype "passive"))
    )
    (net (code "4") (name "+5") (class "Default")
      (node (ref "C17") (pin "2") (pintype "passive"))
      (node (ref "C18") (pin "2") (pintype "passive"))
      (node (ref "C25") (pin "1") (pinfunction "1_1") (pintype "passive"))
      (node (ref "C26") (pin "1") (pinfunction "1_1") (pintype "passive"))
      (node (ref "L1") (pin "1") (pinfunction "1_1") (pintype "passive"))
      (node (ref "L2") (pin "2") (pinfunction "2_2") (pintype "passive"))
      (node (ref "R16") (pin "1") (pinfunction "1_1") (pintype "passive"))
      (node (ref "R7") (pin "2") (pinfunction "2_2") (pintype "passive"))
      (node (ref "SENSORS") (pin "4") (pintype "input"))
      (node (ref "SENSORS") (pin "6") (pintype "input"))
      (node (ref "U1") (pin "161") (pinfunction "VDD_(5V)_161") (pintype "passive"))
      (node (ref "U1") (pin "162") (pinfunction "VDD_(5V)_162") (pintype "passive"))
      (node (ref "U3") (pin "5") (pinfunction "VIN_5") (pintype "power_in"))
      (node (ref "WHEEL") (pin "1") (pintype "input"))
    )
    (net (code "5") (name "+12") (class "Default")
      (node (ref "C23") (pin "2") (pinfunction "A_2") (pintype "passive"))
      (node (ref "R18") (pin "2") (pinfunction "2_2") (pintype "passive"))
      (node (ref "U7") (pin "4") (pinfunction "TAB_4") (pintype "power_in"))
    )
    (net (code "6") (name "+12_in") (class "Default")
      (node (ref "C21") (pin "2") (pinfunction "A_2") (pintype "passive"))
      (node (ref "C22") (pin "2") (pinfunction "A_2") (pintype "passive"))
      (node (ref "C29") (pin "2") (pinfunction "2_2") (pintype "passive"))
      (node (ref "C30") (pin "2") (pinfunction "2_2") (pintype "passive"))
      (node (ref "C60") (pin "2") (pinfunction "2_2") (pintype "passive"))
      (node (ref "C61") (pin "2") (pinfunction "2_2") (pintype "passive"))
      (node (ref "IN") (pin "5") (pinfunction "5_5") (pintype "passive"))
      (node (ref "R5") (pin "2") (pinfunction "2_2") (pintype "passive"))
      (node (ref "R8") (pin "2") (pinfunction "2_2") (pintype "passive"))
      (node (ref "U7") (pin "3") (pinfunction "IN_3") (pintype "power_in"))
      (node (ref "U8") (pin "1") (pinfunction "VIN_1") (pintype "power_in"))
      (node (ref "U9") (pin "1") (pinfunction "VIN_1") (pintype "power_in"))
    )
    (net (code "7") (name "/3.3V_LED") (class "Default")
      (node (ref "3V3") (pin "2") (pinfunction "A_2") (pintype "passive"))
      (node (ref "R14") (pin "1") (pinfunction "1_1") (pintype "passive"))
    )
    (net (code "8") (name "/5V_LED") (class "Default")
      (node (ref "5V") (pin "2") (pinfunction "A_2") (pintype "passive"))
      (node (ref "R16") (pin "2") (pinfunction "2_2") (pintype "passive"))
    )
    (net (code "9") (name "/12V_LED") (class "Default")
      (node (ref "12V") (pin "2") (pinfunction "A_2") (pintype "passive"))
      (node (ref "R18") (pin "1") (pinfunction "1_1") (pintype "passive"))
    )
    (net (code "10") (name "/ADC_APPS1") (class "Default")
      (node (ref "C45") (pin "2") (pintype "passive"))
      (node (ref "R26") (pin "1") (pinfunction "1_1") (pintype "passive"))
      (node (ref "R33") (pin "2") (pinfunction "2_2") (pintype "passive"))
      (node (ref "U1") (pin "83") (pinfunction "ANA1_83") (pintype "passive"))
    )
    (net (code "11") (name "/ADC_APPS2") (class "Default")
      (node (ref "C48") (pin "2") (pintype "passive"))
      (node (ref "R27") (pin "1") (pinfunction "1_1") (pintype "passive"))
      (node (ref "R32") (pin "2") (pinfunction "2_2") (pintype "passive"))
      (node (ref "U1") (pin "84") (pinfunction "ANA0_84") (pintype "passive"))
    )
    (net (code "12") (name "/ADC_FBPS") (class "Default")
      (node (ref "C47") (pin "2") (pintype "passive"))
      (node (ref "R28") (pin "1") (pinfunction "1_1") (pintype "passive"))
      (node (ref "R31") (pin "2") (pinfunction "2_2") (pintype "passive"))
      (node (ref "U1") (pin "86") (pinfunction "PA4_86") (pintype "passive"))
    )
    (net (code "13") (name "/ADC_RBPS") (class "Default")
      (node (ref "C46") (pin "2") (pintype "passive"))
      (node (ref "R29") (pin "1") (pinfunction "1_1") (pintype "passive"))
      (node (ref "R30") (pin "2") (pinfunction "2_2") (pintype "passive"))
      (node (ref "U1") (pin "87") (pinfunction "PA5_87") (pintype "passive"))
    )
    (net (code "14") (name "/AMS_MONITOR") (class "Default")
      (node (ref "R23") (pin "1") (pinfunction "1_1") (pintype "passive"))
      (node (ref "R24") (pin "2") (pinfunction "2_2") (pintype "passive"))
      (node (ref "U1") (pin "134") (pinfunction "PG3_134") (pintype "passive"))
    )
    (net (code "15") (name "/APPS1_IN") (class "Default")
      (node (ref "R26") (pin "2") (pinfunction "2_2") (pintype "passive"))
      (node (ref "SENSORS") (pin "1") (pintype "input"))
    )
    (net (code "16") (name "/APPS2_IN") (class "Default")
      (node (ref "R27") (pin "2") (pinfunction "2_2") (pintype "passive"))
      (node (ref "SENSORS") (pin "2") (pintype "input"))
    )
    (net (code "17") (name "/AUD_FAULT") (class "Default")
      (node (ref "U1") (pin "112") (pinfunction "PF12_112") (pintype "passive"))
    )
    (net (code "18") (name "/AUD_I2C_SCL") (class "Default")
      (node (ref "U1") (pin "110") (pinfunction "PF14_110") (pintype "passive"))
    )
    (net (code "19") (name "/AUD_I2C_SDA") (class "Default")
      (node (ref "U1") (pin "109") (pinfunction "PF15_109") (pintype "passive"))
    )
    (net (code "20") (name "/AUD_nSD") (class "Default")
      (node (ref "U1") (pin "111") (pinfunction "PF13_111") (pintype "passive"))
    )
    (net (code "21") (name "/BACKLIGHT+") (class "Default")
      (node (ref "C16") (pin "2") (pintype "passive"))
      (node (ref "D1") (pin "1") (pinfunction "K_1") (pintype "passive"))
      (node (ref "J1") (pin "39") (pinfunction "39_39") (pintype "passive"))
      (node (ref "J1") (pin "40") (pinfunction "40_40") (pintype "passive"))
    )
    (net (code "22") (name "/BACKLIGHT-") (class "Default")
      (node (ref "J1") (pin "31") (pinfunction "31_31") (pintype "passive"))
      (node (ref "J1") (pin "32") (pinfunction "32_32") (pintype "passive"))
      (node (ref "R4") (pin "2") (pinfunction "2_2") (pintype "passive"))
      (node (ref "U3") (pin "3") (pinfunction "FB_3") (pintype "input"))
    )
    (net (code "23") (name "/BOOT0") (class "Default")
      (node (ref "R1") (pin "1") (pinfunction "1_1") (pintype "passive"))
      (node (ref "S1") (pin "1") (pinfunction "1_1") (pintype "passive"))
      (node (ref "U1") (pin "78") (pinfunction "BOOT0_78") (pintype "passive"))
    )
    (net (code "24") (name "/BOOT1") (class "Default")
      (node (ref "R2") (pin "1") (pinfunction "1_1") (pintype "passive"))
      (node (ref "S1") (pin "6") (pinfunction "2_6") (pintype "passive"))
      (node (ref "U1") (pin "77") (pinfunction "BOOT1_77") (pintype "passive"))
    )
    (net (code "25") (name "/BOOT2") (class "Default")
      (node (ref "R3") (pin "1") (pinfunction "1_1") (pintype "passive"))
      (node (ref "S1") (pin "3") (pinfunction "4_3") (pintype "passive"))
      (node (ref "U1") (pin "79") (pinfunction "BOOT2_79") (pintype "passive"))
    )
    (net (code "26") (name "/CAN1_N") (class "Default")
      (node (ref "IN") (pin "2") (pinfunction "2_2") (pintype "passive"))
      (node (ref "U4") (pin "6") (pinfunction "CANL_6") (pintype "bidirectional"))
    )
    (net (code "27") (name "/CAN1_P") (class "Default")
      (node (ref "IN") (pin "1") (pinfunction "1_1") (pintype "passive"))
      (node (ref "U4") (pin "7") (pinfunction "CANH_7") (pintype "bidirectional"))
    )
    (net (code "28") (name "/CAN1_RX") (class "Default")
      (node (ref "U1") (pin "152") (pinfunction "PA11_152") (pintype "passive"))
      (node (ref "U4") (pin "4") (pinfunction "R_4") (pintype "output"))
    )
    (net (code "29") (name "/CAN1_TX") (class "Default")
      (node (ref "U1") (pin "153") (pinfunction "PA12_153") (pintype "passive"))
      (node (ref "U4") (pin "1") (pinfunction "D_1") (pintype "input"))
    )
    (net (code "30") (name "/CAN2_N") (class "Default")
      (node (ref "IN") (pin "4") (pinfunction "4_4") (pintype "passive"))
      (node (ref "U10") (pin "6") (pinfunction "CANL_6") (pintype "bidirectional"))
    )
    (net (code "31") (name "/CAN2_P") (class "Default")
      (node (ref "IN") (pin "3") (pinfunction "3_3") (pintype "passive"))
      (node (ref "U10") (pin "7") (pinfunction "CANH_7") (pintype "bidirectional"))
    )
    (net (code "32") (name "/CAN2_RX") (class "Default")
      (node (ref "U1") (pin "17") (pinfunction "PB5_17") (pintype "passive"))
      (node (ref "U10") (pin "4") (pinfunction "R_4") (pintype "output"))
    )
    (net (code "33") (name "/CAN2_TX") (class "Default")
      (node (ref "U1") (pin "16") (pinfunction "PB6_16") (pintype "passive"))
      (node (ref "U10") (pin "1") (pinfunction "D_1") (pintype "input"))
    )
    (net (code "34") (name "/DISP_EN") (class "Default")
      (node (ref "U1") (pin "64") (pinfunction "PZ2_64") (pintype "passive"))
      (node (ref "U2") (pin "2") (pinfunction "EN_2") (pintype "passive"))
    )
    (net (code "35") (name "/DISP_IRQ") (class "Default")
      (node (ref "U1") (pin "65") (pinfunction "PZ3_65") (pintype "passive"))
      (node (ref "U2") (pin "33") (pinfunction "IRQ_33") (pintype "passive"))
    )
    (net (code "36") (name "/DISP_RESET") (class "Default")
      (node (ref "J1") (pin "5") (pinfunction "5_5") (pintype "passive"))
    )
    (net (code "37") (name "/DISP_SCL") (class "Default")
      (node (ref "U1") (pin "68") (pinfunction "PZ4_____(I2C4_SCL)_68") (pintype "passive"))
      (node (ref "U2") (pin "15") (pinfunction "SCL_15") (pintype "passive"))
    )
    (net (code "38") (name "/DISP_SDA") (class "Default")
      (node (ref "U1") (pin "69") (pinfunction "PZ5_____(I2C4_SDA)_69") (pintype "passive"))
      (node (ref "U2") (pin "16") (pinfunction "SDA_16") (pintype "passive"))
    )
    (net (code "39") (name "/ETH_LED1") (class "Default")
      (node (ref "DS2") (pin "1") (pinfunction "A_1") (pintype "passive"))
      (node (ref "U1") (pin "107") (pinfunction "ETH_LED1_107") (pintype "passive"))
    )
    (net (code "40") (name "/ETH_LED2") (class "Default")
      (node (ref "DS1") (pin "1") (pinfunction "A_1") (pintype "passive"))
      (node (ref "U1") (pin "106") (pinfunction "ETH_LED2_106") (pintype "passive"))
    )
    (net (code "41") (name "/ETH_TR0_N") (class "Default")
      (node (ref "ETH") (pin "2") (pintype "input"))
      (node (ref "U1") (pin "95") (pinfunction "ETH_TRN0_95") (pintype "passive"))
    )
    (net (code "42") (name "/ETH_TR0_P") (class "Default")
      (node (ref "ETH") (pin "8") (pintype "input"))
      (node (ref "U1") (pin "94") (pinfunction "ETH_TRP0_94") (pintype "passive"))
    )
    (net (code "43") (name "/ETH_TR1_N") (class "Default")
      (node (ref "ETH") (pin "4") (pintype "input"))
      (node (ref "U1") (pin "98") (pinfunction "ETH_TRN2_98") (pintype "passive"))
    )
    (net (code "44") (name "/ETH_TR1_P") (class "Default")
      (node (ref "ETH") (pin "3") (pintype "input"))
      (node (ref "U1") (pin "97") (pinfunction "ETH_TRP1_97") (pintype "passive"))
    )
    (net (code "45") (name "/ETH_TR2_N") (class "Default")
      (node (ref "ETH") (pin "6") (pintype "input"))
      (node (ref "U1") (pin "101") (pinfunction "ETH_TRN2_101") (pintype "passive"))
    )
    (net (code "46") (name "/ETH_TR2_P") (class "Default")
      (node (ref "ETH") (pin "5") (pintype "input"))
      (node (ref "U1") (pin "100") (pinfunction "ETH_TRP2_100") (pintype "passive"))
    )
    (net (code "47") (name "/ETH_TR3_N") (class "Default")
      (node (ref "ETH") (pin "1") (pintype "input"))
      (node (ref "U1") (pin "104") (pinfunction "ETH_TRN3_104") (pintype "passive"))
    )
    (net (code "48") (name "/ETH_TR3_P") (class "Default")
      (node (ref "ETH") (pin "7") (pintype "input"))
      (node (ref "U1") (pin "103") (pinfunction "ETH_TRP3_103") (pintype "passive"))
    )
    (net (code "49") (name "/FBPS_IN") (class "Default")
      (node (ref "R28") (pin "2") (pinfunction "2_2") (pintype "passive"))
      (node (ref "SENSORS") (pin "3") (pintype "input"))
    )
    (net (code "50") (name "/IMD_MONITOR") (class "Default")
      (node (ref "R21") (pin "1") (pinfunction "1_1") (pintype "passive"))
      (node (ref "R22") (pin "2") (pinfunction "2_2") (pintype "passive"))
      (node (ref "U1") (pin "135") (pinfunction "PI11_135") (pintype "passive"))
    )
    (net (code "51") (name "/JTD0") (class "Default")
      (node (ref "J2") (pin "8") (pinfunction "8_8") (pintype "passive"))
      (node (ref "U1") (pin "142") (pinfunction "JTD0_142") (pintype "passive"))
    )
    (net (code "52") (name "/JTDI") (class "Default")
      (node (ref "J2") (pin "7") (pinfunction "7_7") (pintype "passive"))
      (node (ref "U1") (pin "140") (pinfunction "JTDI_140") (pintype "passive"))
    )
    (net (code "53") (name "/JTRST") (class "Default")
      (node (ref "J2") (pin "6") (pinfunction "6_6") (pintype "passive"))
      (node (ref "U1") (pin "141") (pinfunction "JTRST_141") (pintype "passive"))
    )
    (net (code "54") (name "/LCD_BR_PWM") (class "Default")
      (node (ref "U1") (pin "30") (pinfunction "PE6_30") (pintype "passive"))
      (node (ref "U3") (pin "4") (pinfunction "CTRL_4") (pintype "input"))
    )
    (net (code "55") (name "/LED1") (class "Default")
      (node (ref "R13") (pin "2") (pinfunction "2_2") (pintype "passive"))
      (node (ref "U1") (pin "43") (pinfunction "PH10_43") (pintype "passive"))
    )
    (net (code "56") (name "/LED1_A") (class "Default")
      (node (ref "DBG_1") (pin "2") (pinfunction "A_2") (pintype "passive"))
      (node (ref "R13") (pin "1") (pinfunction "1_1") (pintype "passive"))
    )
    (net (code "57") (name "/LED2") (class "Default")
      (node (ref "R15") (pin "2") (pinfunction "2_2") (pintype "passive"))
      (node (ref "U1") (pin "44") (pinfunction "PH12_44") (pintype "passive"))
    )
    (net (code "58") (name "/LED2_A") (class "Default")
      (node (ref "DBG_2") (pin "2") (pinfunction "A_2") (pintype "passive"))
      (node (ref "R15") (pin "1") (pinfunction "1_1") (pintype "passive"))
    )
    (net (code "59") (name "/LED3") (class "Default")
      (node (ref "R17") (pin "2") (pinfunction "2_2") (pintype "passive"))
      (node (ref "U1") (pin "45") (pinfunction "PI5_45") (pintype "passive"))
    )
    (net (code "60") (name "/LED3_A") (class "Default")
      (node (ref "DBG_3") (pin "2") (pinfunction "A_2") (pintype "passive"))
      (node (ref "R17") (pin "1") (pinfunction "1_1") (pintype "passive"))
    )
    (net (code "61") (name "/LED_AMS") (class "Default")
      (node (ref "IN") (pin "7") (pinfunction "7_7") (pintype "passive"))
      (node (ref "R23") (pin "2") (pinfunction "2_2") (pintype "passive"))
    )
    (net (code "62") (name "/LED_BR_PWM") (class "Default")
      (node (ref "Q1") (pin "1") (pinfunction "G_1") (pintype "passive"))
      (node (ref "U1") (pin "132") (pinfunction "PG8_132") (pintype "passive"))
    )
    (net (code "63") (name "/LED_FAULT") (class "Default")
      (node (ref "R19") (pin "2") (pinfunction "2_2") (pintype "passive"))
      (node (ref "U1") (pin "131") (pinfunction "PG2_131") (pintype "passive"))
    )
    (net (code "64") (name "/LED_IMD") (class "Default")
      (node (ref "IN") (pin "6") (pinfunction "6_6") (pintype "passive"))
      (node (ref "R21") (pin "2") (pinfunction "2_2") (pintype "passive"))
    )
    (net (code "65") (name "/LED_TC") (class "Default")
      (node (ref "R20") (pin "2") (pinfunction "2_2") (pintype "passive"))
      (node (ref "U1") (pin "136") (pinfunction "PI8_136") (pintype "passive"))
    )
    (net (code "66") (name "/LVDS_RX0_N") (class "Default")
      (node (ref "J1") (pin "8") (pinfunction "8_8") (pintype "passive"))
      (node (ref "U2") (pin "47") (pinfunction "A_Y0N_47") (pintype "passive"))
    )
    (net (code "67") (name "/LVDS_RX0_P") (class "Default")
      (node (ref "J1") (pin "9") (pinfunction "9_9") (pintype "passive"))
      (node (ref "U2") (pin "46") (pinfunction "A_Y0P_46") (pintype "passive"))
    )
    (net (code "68") (name "/LVDS_RX1_N") (class "Default")
      (node (ref "J1") (pin "11") (pinfunction "11_11") (pintype "passive"))
      (node (ref "U2") (pin "45") (pinfunction "A_Y1N_45") (pintype "passive"))
    )
    (net (code "69") (name "/LVDS_RX1_P") (class "Default")
      (node (ref "J1") (pin "12") (pinfunction "12_12") (pintype "passive"))
      (node (ref "U2") (pin "44") (pinfunction "A_Y1P_44") (pintype "passive"))
    )
    (net (code "70") (name "/LVDS_RX2_N") (class "Default")
      (node (ref "J1") (pin "14") (pinfunction "14_14") (pintype "passive"))
      (node (ref "U2") (pin "42") (pinfunction "A_Y2N_42") (pintype "passive"))
    )
    (net (code "71") (name "/LVDS_RX2_P") (class "Default")
      (node (ref "J1") (pin "15") (pinfunction "15_15") (pintype "passive"))
      (node (ref "U2") (pin "41") (pinfunction "A_Y2P_41") (pintype "passive"))
    )
    (net (code "72") (name "/LVDS_RX3_N") (class "Default")
      (node (ref "J1") (pin "20") (pinfunction "20_20") (pintype "passive"))
      (node (ref "U2") (pin "37") (pinfunction "A_Y3N_37") (pintype "passive"))
    )
    (net (code "73") (name "/LVDS_RX3_P") (class "Default")
      (node (ref "J1") (pin "21") (pinfunction "21_21") (pintype "passive"))
      (node (ref "U2") (pin "36") (pinfunction "A_Y3P_36") (pintype "passive"))
    )
    (net (code "74") (name "/LVDS_RXCLK_N") (class "Default")
      (node (ref "J1") (pin "17") (pinfunction "17_17") (pintype "passive"))
      (node (ref "U2") (pin "39") (pinfunction "A_YCLKN_39") (pintype "passive"))
    )
    (net (code "75") (name "/LVDS_RXCLK_P") (class "Default")
      (node (ref "J1") (pin "18") (pinfunction "18_18") (pintype "passive"))
      (node (ref "U2") (pin "38") (pinfunction "A_YCLKP_38") (pintype "passive"))
    )
    (net (code "76") (name "/MIPI_CLK_N") (class "Default")
      (node (ref "U1") (pin "9") (pinfunction "DSI_CLK_N_9") (pintype "passive"))
      (node (ref "U2") (pin "25") (pinfunction "DCLKN_25") (pintype "passive"))
    )
    (net (code "77") (name "/MIPI_CLK_P") (class "Default")
      (node (ref "U1") (pin "8") (pinfunction "DSI_CLK_P_8") (pintype "passive"))
      (node (ref "U2") (pin "24") (pinfunction "DCLKP_24") (pintype "passive"))
    )
    (net (code "78") (name "/MIPI_D0_N") (class "Default")
      (node (ref "U1") (pin "3") (pinfunction "DSI_D0_N_3") (pintype "passive"))
      (node (ref "U2") (pin "20") (pinfunction "D0IN_20") (pintype "passive"))
    )
    (net (code "79") (name "/MIPI_D0_P") (class "Default")
      (node (ref "U1") (pin "2") (pinfunction "DSI_D0_P_2") (pintype "passive"))
      (node (ref "U2") (pin "19") (pinfunction "D0IP_19") (pintype "passive"))
    )
    (net (code "80") (name "/MIPI_D1_N") (class "Default")
      (node (ref "U1") (pin "6") (pinfunction "DSI_D1_N_6") (pintype "passive"))
      (node (ref "U2") (pin "22") (pinfunction "D1IN_22") (pintype "passive"))
    )
    (net (code "81") (name "/MIPI_D1_P") (class "Default")
      (node (ref "U1") (pin "5") (pinfunction "DSI_D1_P_5") (pintype "passive"))
      (node (ref "U2") (pin "21") (pinfunction "D1IP_21") (pintype "passive"))
    )
    (net (code "82") (name "/RBPS_IN") (class "Default")
      (node (ref "R29") (pin "2") (pinfunction "2_2") (pintype "passive"))
      (node (ref "SENSORS") (pin "7") (pintype "input"))
    )
    (net (code "83") (name "/RTD_LED_B") (class "Default")
      (node (ref "RTD_LED") (pin "3") (pintype "input"))
      (node (ref "U1") (pin "35") (pinfunction "PE13_35") (pintype "passive"))
    )
    (net (code "84") (name "/RTD_LED_G") (class "Default")
      (node (ref "RTD_LED") (pin "2") (pintype "input"))
      (node (ref "U1") (pin "33") (pinfunction "PE11_33") (pintype "passive"))
    )
    (net (code "85") (name "/RTD_LED_R") (class "Default")
      (node (ref "RTD_LED") (pin "1") (pintype "input"))
      (node (ref "U1") (pin "32") (pinfunction "PE14_32") (pintype "passive"))
    )
    (net (code "86") (name "/SAI_FS") (class "Default")
      (node (ref "U1") (pin "117") (pinfunction "PF9_117") (pintype "passive"))
    )
    (net (code "87") (name "/SAI_MCLK") (class "Default")
      (node (ref "U1") (pin "113") (pinfunction "PF7_113") (pintype "passive"))
    )
    (net (code "88") (name "/SAI_SCLK") (class "Default")
      (node (ref "U1") (pin "114") (pinfunction "PF8_114") (pintype "passive"))
    )
    (net (code "89") (name "/SAI_SD") (class "Default")
      (node (ref "U1") (pin "115") (pinfunction "PF6_115") (pintype "passive"))
    )
    (net (code "90") (name "/SDIO_CLK") (class "Default")
      (node (ref "SD1") (pin "5") (pinfunction "CLK_5") (pintype "passive"))
      (node (ref "U1") (pin "27") (pinfunction "PG15__(SDMMC3_CK)_27") (pintype "passive"))
    )
    (net (code "91") (name "/SDIO_CMD") (class "Default")
      (node (ref "SD1") (pin "3") (pinfunction "CMD_3") (pintype "passive"))
      (node (ref "U1") (pin "24") (pinfunction "PF1_____(SDMMC3_D1)_24") (pintype "passive"))
    )
    (net (code "92") (name "/SDIO_D0") (class "Default")
      (node (ref "SD1") (pin "7") (pinfunction "DAT0_7") (pintype "passive"))
      (node (ref "U1") (pin "23") (pinfunction "PF0_____(SDMMC3_D0)_23") (pintype "passive"))
    )
    (net (code "93") (name "/SDIO_D1") (class "Default")
      (node (ref "SD1") (pin "8") (pinfunction "DAT1_8") (pintype "passive"))
      (node (ref "U1") (pin "25") (pinfunction "PF4_____(SDMMC3_D1)_25") (pintype "passive"))
    )
    (net (code "94") (name "/SDIO_D2") (class "Default")
      (node (ref "SD1") (pin "1") (pinfunction "DAT2_1") (pintype "passive"))
      (node (ref "U1") (pin "26") (pinfunction "PF5_____(SDMMC3_D2)_26") (pintype "passive"))
    )
    (net (code "95") (name "/SDIO_D3") (class "Default")
      (node (ref "SD1") (pin "2") (pinfunction "CD/DAT3_2") (pintype "passive"))
      (node (ref "U1") (pin "22") (pinfunction "PD7_____(SDMMC3_D3)_22") (pintype "passive"))
    )
    (net (code "96") (name "/SDIO_DET") (class "Default")
      (node (ref "R25") (pin "1") (pinfunction "1_1") (pintype "passive"))
      (node (ref "SD1") (pin "9") (pinfunction "DETECT_9") (pintype "passive"))
    )
    (net (code "97") (name "/STBY") (class "Default")
      (node (ref "J1") (pin "6") (pinfunction "6_6") (pintype "passive"))
    )
    (net (code "98") (name "/SWCLK") (class "Default")
      (node (ref "J2") (pin "9") (pinfunction "9_9") (pintype "passive"))
      (node (ref "U1") (pin "139") (pinfunction "SWCLK_139") (pintype "passive"))
    )
    (net (code "99") (name "/SWDIO") (class "Default")
      (node (ref "J2") (pin "10") (pinfunction "10_10") (pintype "passive"))
      (node (ref "U1") (pin "138") (pinfunction "SWDIO_138") (pintype "passive"))
    )
    (net (code "100") (name "/USB1_N") (class "Default")
      (node (ref "U1") (pin "127") (pinfunction "USB1_N_127") (pintype "passive"))
      (node (ref "WHEEL") (pin "2") (pintype "input"))
    )
    (net (code "101") (name "/USB1_P") (class "Default")
      (node (ref "U1") (pin "126") (pinfunction "USB1_P_126") (pintype "passive"))
      (node (ref "WHEEL") (pin "3") (pintype "input"))
    )
    (net (code "102") (name "GND") (class "Default")
      (node (ref "12V") (pin "1") (pinfunction "C_1") (pintype "passive"))
      (node (ref "3V3") (pin "1") (pinfunction "C_1") (pintype "passive"))
      (node (ref "5V") (pin "1") (pinfunction "C_1") (pintype "passive"))
      (node (ref "C1") (pin "1") (pinfunction "1_1") (pintype "passive"))
      (node (ref "C10") (pin "1") (pinfunction "1_1") (pintype "passive"))
      (node (ref "C11") (pin "1") (pinfunction "1_1") (pintype "passive"))
      (node (ref "C12") (pin "1") (pinfunction "1_1") (pintype "passive"))
      (node (ref "C13") (pin "1") (pintype "passive"))
      (node (ref "C14") (pin "1") (pintype "passive"))
      (node (ref "C16") (pin "1") (pintype "passive"))
      (node (ref "C17") (pin "1") (pintype "passive"))
      (node (ref "C18") (pin "1") (pintype "passive"))
      (node (ref "C19") (pin "2") (pinfunction "2_2") (pintype "passive"))
      (node (ref "C2") (pin "1") (pinfunction "1_1") (pintype "passive"))
      (node (ref "C20") (pin "1") (pinfunction "1_1") (pintype "passive"))
      (node (ref "C21") (pin "1") (pinfunction "C_1") (pintype "passive"))
      (node (ref "C22") (pin "1") (pinfunction "C_1") (pintype "passive"))
      (node (ref "C23") (pin "1") (pinfunction "C_1") (pintype "passive"))
      (node (ref "C25") (pin "2") (pinfunction "2_2") (pintype "passive"))
      (node (ref "C26") (pin "2") (pinfunction "2_2") (pintype "passive"))
      (node (ref "C27") (pin "1") (pintype "passive"))
      (node (ref "C28") (pin "1") (pinfunction "1_1") (pintype "passive"))
      (node (ref "C29") (pin "1") (pinfunction "1_1") (pintype "passive"))
      (node (ref "C3") (pin "1") (pinfunction "1_1") (pintype "passive"))
      (node (ref "C30") (pin "1") (pinfunction "1_1") (pintype "passive"))
      (node (ref "C4") (pin "1") (pinfunction "1_1") (pintype "passive"))
      (node (ref "C42") (pin "1") (pintype "passive"))
      (node (ref "C43") (pin "1") (pintype "passive"))
      (node (ref "C44") (pin "1") (pintype "passive"))
      (node (ref "C45") (pin "1") (pintype "passive"))
      (node (ref "C46") (pin "1") (pintype "passive"))
      (node (ref "C47") (pin "1") (pintype "passive"))
      (node (ref "C48") (pin "1") (pintype "passive"))
      (node (ref "C5") (pin "1") (pinfunction "1_1") (pintype "passive"))
      (node (ref "C54") (pin "2") (pinfunction "2_2") (pintype "passive"))
      (node (ref "C59") (pin "2") (pinfunction "2_2") (pintype "passive"))
      (node (ref "C6") (pin "1") (pinfunction "1_1") (pintype "passive"))
      (node (ref "C60") (pin "1") (pinfunction "1_1") (pintype "passive"))
      (node (ref "C61") (pin "1") (pinfunction "1_1") (pintype "passive"))
      (node (ref "C7") (pin "1") (pinfunction "1_1") (pintype "passive"))
      (node (ref "C8") (pin "1") (pinfunction "1_1") (pintype "passive"))
      (node (ref "C9") (pin "1") (pinfunction "1_1") (pintype "passive"))
      (node (ref "DBG_1") (pin "1") (pinfunction "C_1") (pintype "passive"))
      (node (ref "DBG_2") (pin "1") (pinfunction "C_1") (pintype "passive"))
      (node (ref "DBG_3") (pin "1") (pinfunction "C_1") (pintype "passive"))
      (node (ref "IN") (pin "8") (pinfunction "8_8") (pintype "passive"))
      (node (ref "J1") (pin "10") (pinfunction "10_10") (pintype "passive"))
      (node (ref "J1") (pin "13") (pinfunction "13_13") (pintype "passive"))
      (node (ref "J1") (pin "16") (pinfunction "16_16") (pintype "passive"))
      (node (ref "J1") (pin "19") (pinfunction "19_19") (pintype "passive"))
      (node (ref "J1") (pin "22") (pinfunction "22_22") (pintype "passive"))
      (node (ref "J1") (pin "25") (pinfunction "25_25") (pintype "passive"))
      (node (ref "J1") (pin "30") (pinfunction "30_30") (pintype "passive"))
      (node (ref "J1") (pin "MP1") (pinfunction "MP1_MP1") (pintype "passive"))
      (node (ref "J1") (pin "MP2") (pinfunction "MP2_MP2") (pintype "passive"))
      (node (ref "J2") (pin "2") (pinfunction "2_2") (pintype "passive"))
      (node (ref "J2") (pin "3") (pinfunction "3_3") (pintype "passive"))
      (node (ref "J2") (pin "5") (pinfunction "5_5") (pintype "passive"))
      (node (ref "Q1") (pin "2") (pinfunction "S_2") (pintype "passive"))
      (node (ref "R11") (pin "1") (pinfunction "1_1") (pintype "passive"))
      (node (ref "R12") (pin "1") (pinfunction "1_1") (pintype "passive"))
      (node (ref "R25") (pin "2") (pinfunction "2_2") (pintype "passive"))
      (node (ref "R30") (pin "1") (pinfunction "1_1") (pintype "passive"))
      (node (ref "R31") (pin "1") (pinfunction "1_1") (pintype "passive"))
      (node (ref "R32") (pin "1") (pinfunction "1_1") (pintype "passive"))
      (node (ref "R33") (pin "1") (pinfunction "1_1") (pintype "passive"))
      (node (ref "R34") (pin "1") (pinfunction "1_1") (pintype "passive"))
      (node (ref "R4") (pin "1") (pinfunction "1_1") (pintype "passive"))
      (node (ref "R9") (pin "1") (pinfunction "1_1") (pintype "passive"))
      (node (ref "RTD_LED") (pin "4") (pintype "input"))
      (node (ref "S1") (pin "2") (pinfunction "C_2") (pintype "passive"))
      (node (ref "S1") (pin "5") (pinfunction "C_5") (pintype "passive"))
      (node (ref "SD1") (pin "11") (pinfunction "SHLD_11") (pintype "passive"))
      (node (ref "SD1") (pin "12") (pinfunction "SHLD_12") (pintype "passive"))
      (node (ref "SD1") (pin "13") (pinfunction "SHLD_13") (pintype "passive"))
      (node (ref "SD1") (pin "14") (pinfunction "SHLD_14") (pintype "passive"))
      (node (ref "SD1") (pin "6") (pinfunction "VSS_6") (pintype "passive"))
      (node (ref "SENSORS") (pin "5") (pintype "input"))
      (node (ref "SENSORS") (pin "8") (pintype "input"))
      (node (ref "SW1") (pin "A2") (pinfunction "A2_A2") (pintype "passive"))
      (node (ref "U1") (pin "1") (pinfunction "GND_1") (pintype "passive"))
      (node (ref "U1") (pin "10") (pinfunction "GND_10") (pintype "passive"))
      (node (ref "U1") (pin "102") (pinfunction "GND_102") (pintype "passive"))
      (node (ref "U1") (pin "105") (pinfunction "GND_105") (pintype "passive"))
      (node (ref "U1") (pin "108") (pinfunction "GND_108") (pintype "passive"))
      (node (ref "U1") (pin "121") (pinfunction "GND_121") (pintype "passive"))
      (node (ref "U1") (pin "124") (pinfunction "GND_124") (pintype "passive"))
      (node (ref "U1") (pin "125") (pinfunction "GND_125") (pintype "passive"))
      (node (ref "U1") (pin "128") (pinfunction "GND_128") (pintype "passive"))
      (node (ref "U1") (pin "133") (pinfunction "GND_133") (pintype "passive"))
      (node (ref "U1") (pin "137") (pinfunction "GND_137") (pintype "passive"))
      (node (ref "U1") (pin "144") (pinfunction "GND_144") (pintype "passive"))
      (node (ref "U1") (pin "154") (pinfunction "GND_154") (pintype "passive"))
      (node (ref "U1") (pin "159") (pinfunction "GND_159") (pintype "passive"))
      (node (ref "U1") (pin "163") (pinfunction "GND_163") (pintype "passive"))
      (node (ref "U1") (pin "164") (pinfunction "GND_164") (pintype "passive"))
      (node (ref "U1") (pin "29") (pinfunction "GND_29") (pintype "passive"))
      (node (ref "U1") (pin "4") (pinfunction "GND_4") (pintype "passive"))
      (node (ref "U1") (pin "7") (pinfunction "GND_7") (pintype "passive"))
      (node (ref "U1") (pin "74") (pinfunction "GND_74") (pintype "passive"))
      (node (ref "U1") (pin "85") (pinfunction "GND_85") (pintype "passive"))
      (node (ref "U1") (pin "90") (pinfunction "GND_90") (pintype "passive"))
      (node (ref "U1") (pin "93") (pinfunction "GND_93") (pintype "passive"))
      (node (ref "U1") (pin "96") (pinfunction "GND_96") (pintype "passive"))
      (node (ref "U1") (pin "99") (pinfunction "GND_99") (pintype "passive"))
      (node (ref "U10") (pin "2") (pinfunction "GND_2") (pintype "power_in"))
      (node (ref "U2") (pin "17") (pinfunction "REFCLK_17") (pintype "passive"))
      (node (ref "U2") (pin "23") (pinfunction "GND_23") (pintype "passive"))
      (node (ref "U2") (pin "26") (pinfunction "GND_26") (pintype "passive"))
      (node (ref "U2") (pin "52") (pinfunction "GND_52") (pintype "passive"))
      (node (ref "U2") (pin "64") (pinfunction "ADDR_64") (pintype "passive"))
      (node (ref "U2") (pin "65") (pinfunction "GND_65") (pintype "passive"))
      (node (ref "U3") (pin "2") (pinfunction "GND_2") (pintype "power_in"))
      (node (ref "U4") (pin "2") (pinfunction "GND_2") (pintype "power_in"))
      (node (ref "U6") (pin "1") (pinfunction "GND_1") (pintype "power_in"))
      (node (ref "U7") (pin "1") (pinfunction "ADJ_1") (pintype "input"))
      (node (ref "U8") (pin "3") (pinfunction "GND_3") (pintype "power_in"))
      (node (ref "U9") (pin "3") (pinfunction "GND_3") (pintype "power_in"))
      (node (ref "WHEEL") (pin "4") (pintype "input"))
    )
    (net (code "103") (name "Net-(AMS-A)") (class "Default")
      (node (ref "AMS") (pin "1") (pinfunction "A_1") (pintype "passive"))
      (node (ref "R24") (pin "1") (pinfunction "1_1") (pintype "passive"))
    )
    (net (code "104") (name "Net-(AMS-K)") (class "Default")
      (node (ref "AMS") (pin "2") (pinfunction "K_2") (pintype "passive"))
      (node (ref "FAULT") (pin "2") (pinfunction "K_2") (pintype "passive"))
      (node (ref "IMD") (pin "2") (pinfunction "K_2") (pintype "passive"))
      (node (ref "Q1") (pin "3") (pinfunction "D_3") (pintype "passive"))
      (node (ref "TC") (pin "2") (pinfunction "K_2") (pintype "passive"))
    )
    (net (code "105") (name "Net-(C15-Pad1)") (class "Default")
      (node (ref "C15") (pin "1") (pintype "passive"))
      (node (ref "SW1") (pin "A1") (pinfunction "A1_A1") (pintype "passive"))
    )
    (net (code "106") (name "Net-(D1-A)") (class "Default")
      (node (ref "D1") (pin "2") (pinfunction "A_2") (pintype "passive"))
      (node (ref "L1") (pin "2") (pinfunction "2_2") (pintype "passive"))
      (node (ref "U3") (pin "1") (pinfunction "SW_1") (pintype "passive"))
    )
    (net (code "107") (name "Net-(DS1-K)") (class "Default")
      (node (ref "DS1") (pin "2") (pinfunction "K_2") (pintype "passive"))
      (node (ref "R11") (pin "2") (pinfunction "2_2") (pintype "passive"))
    )
    (net (code "108") (name "Net-(DS2-K)") (class "Default")
      (node (ref "DS2") (pin "2") (pinfunction "K_2") (pintype "passive"))
      (node (ref "R12") (pin "2") (pinfunction "2_2") (pintype "passive"))
    )
    (net (code "109") (name "Net-(FAULT-A)") (class "Default")
      (node (ref "FAULT") (pin "1") (pinfunction "A_1") (pintype "passive"))
      (node (ref "R19") (pin "1") (pinfunction "1_1") (pintype "passive"))
    )
    (net (code "110") (name "Net-(IMD-A)") (class "Default")
      (node (ref "IMD") (pin "1") (pinfunction "A_1") (pintype "passive"))
      (node (ref "R22") (pin "1") (pinfunction "1_1") (pintype "passive"))
    )
    (net (code "111") (name "Net-(TC-A)") (class "Default")
      (node (ref "R20") (pin "1") (pinfunction "1_1") (pintype "passive"))
      (node (ref "TC") (pin "1") (pinfunction "A_1") (pintype "passive"))
    )
    (net (code "112") (name "Net-(U1C-NRST)") (class "Default")
      (node (ref "C15") (pin "2") (pintype "passive"))
      (node (ref "SW1") (pin "B1") (pinfunction "B1_B1") (pintype "passive"))
      (node (ref "SW1") (pin "B2") (pinfunction "B2_B2") (pintype "passive"))
      (node (ref "U1") (pin "82") (pinfunction "NRST_82") (pintype "passive"))
    )
    (net (code "113") (name "Net-(U2-VCORE)") (class "Default")
      (node (ref "C14") (pin "2") (pintype "passive"))
      (node (ref "U2") (pin "31") (pinfunction "VCORE_31") (pintype "passive"))
    )
    (net (code "114") (name "Net-(U8-BST)") (class "Default")
      (node (ref "C24") (pin "2") (pinfunction "2_2") (pintype "passive"))
      (node (ref "U8") (pin "4") (pinfunction "BST_4") (pintype "passive"))
    )
    (net (code "115") (name "Net-(U8-EN)") (class "Default")
      (node (ref "R8") (pin "1") (pinfunction "1_1") (pintype "passive"))
      (node (ref "U8") (pin "5") (pinfunction "EN_5") (pintype "input"))
    )
    (net (code "116") (name "Net-(U8-FB)") (class "Default")
      (node (ref "R7") (pin "1") (pinfunction "1_1") (pintype "passive"))
      (node (ref "R9") (pin "2") (pinfunction "2_2") (pintype "passive"))
      (node (ref "U8") (pin "6") (pinfunction "FB_6") (pintype "passive"))
    )
    (net (code "117") (name "Net-(U8-SW)") (class "Default")
      (node (ref "C24") (pin "1") (pinfunction "1_1") (pintype "passive"))
      (node (ref "L2") (pin "1") (pinfunction "1_1") (pintype "passive"))
      (node (ref "U8") (pin "2") (pinfunction "SW_2") (pintype "passive"))
    )
    (net (code "118") (name "Net-(U9-BST)") (class "Default")
      (node (ref "C53") (pin "2") (pinfunction "2_2") (pintype "passive"))
      (node (ref "U9") (pin "4") (pinfunction "BST_4") (pintype "passive"))
    )
    (net (code "119") (name "Net-(U9-EN)") (class "Default")
      (node (ref "R5") (pin "1") (pinfunction "1_1") (pintype "passive"))
      (node (ref "U9") (pin "5") (pinfunction "EN_5") (pintype "input"))
    )
    (net (code "120") (name "Net-(U9-FB)") (class "Default")
      (node (ref "R34") (pin "2") (pinfunction "2_2") (pintype "passive"))
      (node (ref "R6") (pin "1") (pinfunction "1_1") (pintype "passive"))
      (node (ref "U9") (pin "6") (pinfunction "FB_6") (pintype "passive"))
    )
    (net (code "121") (name "Net-(U9-SW)") (class "Default")
      (node (ref "C53") (pin "1") (pinfunction "1_1") (pintype "passive"))
      (node (ref "L5") (pin "1") (pinfunction "1_1") (pintype "passive"))
      (node (ref "U9") (pin "2") (pinfunction "SW_2") (pintype "passive"))
    )
    (net (code "122") (name "WIFI_RESET") (class "Default")
      (node (ref "U1") (pin "119") (pinfunction "PF10_119") (pintype "passive"))
    )
    (net (code "123") (name "WIFI_SDIO_CLK") (class "Default")
      (node (ref "U1") (pin "149") (pinfunction "PC12___(SDMMC1_CK)_149") (pintype "passive"))
    )
    (net (code "124") (name "WIFI_SDIO_CMD") (class "Default")
      (node (ref "U1") (pin "150") (pinfunction "PD2_____(SDMMC1_CMD)_150") (pintype "passive"))
    )
    (net (code "125") (name "WIFI_SDIO_D0") (class "Default")
      (node (ref "U1") (pin "145") (pinfunction "PC8_____(SDMMC1_D0)_145") (pintype "passive"))
    )
    (net (code "126") (name "WIFI_SDIO_D1") (class "Default")
      (node (ref "U1") (pin "146") (pinfunction "PC9_____(SDMMC1_D1)_146") (pintype "passive"))
    )
    (net (code "127") (name "WIFI_SDIO_D2") (class "Default")
      (node (ref "U1") (pin "147") (pinfunction "PC10___(SDMMC1_D2)_147") (pintype "passive"))
    )
    (net (code "128") (name "WIFI_SDIO_D3") (class "Default")
      (node (ref "U1") (pin "148") (pinfunction "PC11___(SDMMC1_D3)_148") (pintype "passive"))
    )
    (net (code "129") (name "WIFI_UART_CTS") (class "Default")
      (node (ref "U1") (pin "59") (pinfunction "PG10_59") (pintype "passive"))
    )
    (net (code "130") (name "WIFI_UART_RTS") (class "Default")
      (node (ref "U1") (pin "60") (pinfunction "PG7_60") (pintype "passive"))
    )
    (net (code "131") (name "WIFI_UART_RXD") (class "Default")
      (node (ref "U1") (pin "66") (pinfunction "PE0_66") (pintype "passive"))
    )
    (net (code "132") (name "WIFI_UART_TXD") (class "Default")
      (node (ref "U1") (pin "67") (pinfunction "PE1_67") (pintype "passive"))
    )
    (net (code "133") (name "WIFI_USB2_N") (class "Default")
      (node (ref "U1") (pin "123") (pinfunction "USB2_N_123") (pintype "passive"))
    )
    (net (code "134") (name "WIFI_USB2_P") (class "Default")
      (node (ref "U1") (pin "122") (pinfunction "USB2_P_122") (pintype "passive"))
    )
    (net (code "135") (name "unconnected-(J1-Pad1)") (class "Default")
      (node (ref "J1") (pin "1") (pinfunction "1_1") (pintype "passive+no_connect"))
    )
    (net (code "136") (name "unconnected-(J1-Pad4)") (class "Default")
      (node (ref "J1") (pin "4") (pinfunction "4_4") (pintype "passive+no_connect"))
    )
    (net (code "137") (name "unconnected-(J1-Pad7)") (class "Default")
      (node (ref "J1") (pin "7") (pinfunction "7_7") (pintype "passive+no_connect"))
    )
    (net (code "138") (name "unconnected-(J1-Pad23)") (class "Default")
      (node (ref "J1") (pin "23") (pinfunction "23_23") (pintype "passive+no_connect"))
    )
    (net (code "139") (name "unconnected-(J1-Pad24)") (class "Default")
      (node (ref "J1") (pin "24") (pinfunction "24_24") (pintype "passive+no_connect"))
    )
    (net (code "140") (name "unconnected-(J1-Pad26)") (class "Default")
      (node (ref "J1") (pin "26") (pinfunction "26_26") (pintype "passive+no_connect"))
    )
    (net (code "141") (name "unconnected-(J1-Pad27)") (class "Default")
      (node (ref "J1") (pin "27") (pinfunction "27_27") (pintype "passive+no_connect"))
    )
    (net (code "142") (name "unconnected-(J1-Pad28)") (class "Default")
      (node (ref "J1") (pin "28") (pinfunction "28_28") (pintype "passive+no_connect"))
    )
    (net (code "143") (name "unconnected-(J1-Pad29)") (class "Default")
      (node (ref "J1") (pin "29") (pinfunction "29_29") (pintype "passive+no_connect"))
    )
    (net (code "144") (name "unconnected-(J1-Pad33)") (class "Default")
      (node (ref "J1") (pin "33") (pinfunction "33_33") (pintype "passive+no_connect"))
    )
    (net (code "145") (name "unconnected-(J1-Pad34)") (class "Default")
      (node (ref "J1") (pin "34") (pinfunction "34_34") (pintype "passive+no_connect"))
    )
    (net (code "146") (name "unconnected-(J1-Pad35)") (class "Default")
      (node (ref "J1") (pin "35") (pinfunction "35_35") (pintype "passive+no_connect"))
    )
    (net (code "147") (name "unconnected-(J1-Pad36)") (class "Default")
      (node (ref "J1") (pin "36") (pinfunction "36_36") (pintype "passive+no_connect"))
    )
    (net (code "148") (name "unconnected-(J1-Pad37)") (class "Default")
      (node (ref "J1") (pin "37") (pinfunction "37_37") (pintype "passive+no_connect"))
    )
    (net (code "149") (name "unconnected-(J1-Pad38)") (class "Default")
      (node (ref "J1") (pin "38") (pinfunction "38_38") (pintype "passive+no_connect"))
    )
    (net (code "150") (name "unconnected-(J2-Pad4)") (class "Default")
      (node (ref "J2") (pin "4") (pinfunction "4_4") (pintype "passive"))
    )
    (net (code "151") (name "unconnected-(S1-X-Pad4)") (class "Default")
      (node (ref "S1") (pin "4") (pinfunction "X_4") (pintype "passive+no_connect"))
    )
    (net (code "152") (name "unconnected-(U1A-PA0-Pad143)") (class "Default")
      (node (ref "U1") (pin "143") (pinfunction "PA0_143") (pintype "passive"))
    )
    (net (code "153") (name "unconnected-(U1A-PA3-Pad151)") (class "Default")
      (node (ref "U1") (pin "151") (pinfunction "PA3_151") (pintype "passive"))
    )
    (net (code "154") (name "unconnected-(U1A-PA10-Pad129)") (class "Default")
      (node (ref "U1") (pin "129") (pinfunction "PA10_129") (pintype "passive"))
    )
    (net (code "155") (name "unconnected-(U1A-PA13-Pad81)") (class "Default")
      (node (ref "U1") (pin "81") (pinfunction "PA13_81") (pintype "passive"))
    )
    (net (code "156") (name "unconnected-(U1A-PA14-Pad89)") (class "Default")
      (node (ref "U1") (pin "89") (pinfunction "PA14_89") (pintype "passive"))
    )
    (net (code "157") (name "unconnected-(U1A-PA15-Pad88)") (class "Default")
      (node (ref "U1") (pin "88") (pinfunction "PA15_88") (pintype "passive"))
    )
    (net (code "158") (name "unconnected-(U1A-PB2-Pad92)") (class "Default")
      (node (ref "U1") (pin "92") (pinfunction "PB2_92") (pintype "passive"))
    )
    (net (code "159") (name "unconnected-(U1A-PB7-Pad14)") (class "Default")
      (node (ref "U1") (pin "14") (pinfunction "PB7_14") (pintype "passive"))
    )
    (net (code "160") (name "unconnected-(U1A-PB8-Pad20)") (class "Default")
      (node (ref "U1") (pin "20") (pinfunction "PB8_20") (pintype "passive"))
    )
    (net (code "161") (name "unconnected-(U1A-PB9-Pad15)") (class "Default")
      (node (ref "U1") (pin "15") (pinfunction "PB9_15") (pintype "passive"))
    )
    (net (code "162") (name "unconnected-(U1A-PB10-Pad18)") (class "Default")
      (node (ref "U1") (pin "18") (pinfunction "PB10_18") (pintype "passive"))
    )
    (net (code "163") (name "unconnected-(U1A-PB12-Pad21)") (class "Default")
      (node (ref "U1") (pin "21") (pinfunction "PB12_21") (pintype "passive"))
    )
    (net (code "164") (name "unconnected-(U1A-PB13-Pad19)") (class "Default")
      (node (ref "U1") (pin "19") (pinfunction "PB13_19") (pintype "passive"))
    )
    (net (code "165") (name "unconnected-(U1A-PC3-Pad80)") (class "Default")
      (node (ref "U1") (pin "80") (pinfunction "PC3_80") (pintype "passive"))
    )
    (net (code "166") (name "unconnected-(U1A-PC6-Pad12)") (class "Default")
      (node (ref "U1") (pin "12") (pinfunction "PC6_12") (pintype "passive"))
    )
    (net (code "167") (name "unconnected-(U1A-PC7-Pad13)") (class "Default")
      (node (ref "U1") (pin "13") (pinfunction "PC7_13") (pintype "passive"))
    )
    (net (code "168") (name "unconnected-(U1A-PD8-Pad70)") (class "Default")
      (node (ref "U1") (pin "70") (pinfunction "PD8_70") (pintype "passive"))
    )
    (net (code "169") (name "unconnected-(U1A-PD9-Pad71)") (class "Default")
      (node (ref "U1") (pin "71") (pinfunction "PD9_71") (pintype "passive"))
    )
    (net (code "170") (name "unconnected-(U1A-PD10-Pad37)") (class "Default")
      (node (ref "U1") (pin "37") (pinfunction "PD10_37") (pintype "passive"))
    )
    (net (code "171") (name "unconnected-(U1A-PD13-Pad11)") (class "Default")
      (node (ref "U1") (pin "11") (pinfunction "PD13_11") (pintype "passive"))
    )
    (net (code "172") (name "unconnected-(U1A-PE4-Pad28)") (class "Default")
      (node (ref "U1") (pin "28") (pinfunction "PE4_28") (pintype "passive"))
    )
    (net (code "173") (name "unconnected-(U1A-PE12-Pad34)") (class "Default")
      (node (ref "U1") (pin "34") (pinfunction "PE12_34") (pintype "passive"))
    )
    (net (code "174") (name "unconnected-(U1A-PE15-Pad31)") (class "Default")
      (node (ref "U1") (pin "31") (pinfunction "PE15_31") (pintype "passive"))
    )
    (net (code "175") (name "unconnected-(U1A-PF2-Pad120)") (class "Default")
      (node (ref "U1") (pin "120") (pinfunction "PF2_120") (pintype "passive"))
    )
    (net (code "176") (name "unconnected-(U1A-PF3-Pad116)") (class "Default")
      (node (ref "U1") (pin "116") (pinfunction "PF3_116") (pintype "passive"))
    )
    (net (code "177") (name "unconnected-(U1A-PF11-Pad118)") (class "Default")
      (node (ref "U1") (pin "118") (pinfunction "PF11_118") (pintype "passive"))
    )
    (net (code "178") (name "unconnected-(U1A-PG11-Pad91)") (class "Default")
      (node (ref "U1") (pin "91") (pinfunction "PG11_91") (pintype "passive"))
    )
    (net (code "179") (name "unconnected-(U1A-PG12-Pad58)") (class "Default")
      (node (ref "U1") (pin "58") (pinfunction "PG12_58") (pintype "passive"))
    )
    (net (code "180") (name "unconnected-(U1A-PH2-Pad73)") (class "Default")
      (node (ref "U1") (pin "73") (pinfunction "PH2_73") (pintype "passive"))
    )
    (net (code "181") (name "unconnected-(U1A-PH3-Pad72)") (class "Default")
      (node (ref "U1") (pin "72") (pinfunction "PH3_72") (pintype "passive"))
    )
    (net (code "182") (name "unconnected-(U1A-PH4-Pad47)") (class "Default")
      (node (ref "U1") (pin "47") (pinfunction "PH4_47") (pintype "passive"))
    )
    (net (code "183") (name "unconnected-(U1A-PH5-Pad48)") (class "Default")
      (node (ref "U1") (pin "48") (pinfunction "PH5_48") (pintype "passive"))
    )
    (net (code "184") (name "unconnected-(U1A-PH6-Pad51)") (class "Default")
      (node (ref "U1") (pin "51") (pinfunction "PH6_51") (pintype "passive"))
    )
    (net (code "185") (name "unconnected-(U1A-PH7-Pad52)") (class "Default")
      (node (ref "U1") (pin "52") (pinfunction "PH7_52") (pintype "passive"))
    )
    (net (code "186") (name "unconnected-(U1A-PH8-Pad39)") (class "Default")
      (node (ref "U1") (pin "39") (pinfunction "PH8_39") (pintype "passive"))
    )
    (net (code "187") (name "unconnected-(U1A-PH9-Pad40)") (class "Default")
      (node (ref "U1") (pin "40") (pinfunction "PH9_40") (pintype "passive"))
    )
    (net (code "188") (name "unconnected-(U1A-PH11-Pad36)") (class "Default")
      (node (ref "U1") (pin "36") (pinfunction "PH11_36") (pintype "passive"))
    )
    (net (code "189") (name "unconnected-(U1A-PH13-Pad50)") (class "Default")
      (node (ref "U1") (pin "50") (pinfunction "PH13_50") (pintype "passive"))
    )
    (net (code "190") (name "unconnected-(U1A-PH14-Pad46)") (class "Default")
      (node (ref "U1") (pin "46") (pinfunction "PH14_46") (pintype "passive"))
    )
    (net (code "191") (name "unconnected-(U1A-PH15-Pad49)") (class "Default")
      (node (ref "U1") (pin "49") (pinfunction "PH15_49") (pintype "passive"))
    )
    (net (code "192") (name "unconnected-(U1A-PI0-Pad53)") (class "Default")
      (node (ref "U1") (pin "53") (pinfunction "PI0_53") (pintype "passive"))
    )
    (net (code "193") (name "unconnected-(U1A-PI1-Pad56)") (class "Default")
      (node (ref "U1") (pin "56") (pinfunction "PI1_56") (pintype "passive"))
    )
    (net (code "194") (name "unconnected-(U1A-PI2-Pad55)") (class "Default")
      (node (ref "U1") (pin "55") (pinfunction "PI2_55") (pintype "passive"))
    )
    (net (code "195") (name "unconnected-(U1A-PI3-Pad54)") (class "Default")
      (node (ref "U1") (pin "54") (pinfunction "PI3_54") (pintype "passive"))
    )
    (net (code "196") (name "unconnected-(U1A-PI4-Pad41)") (class "Default")
      (node (ref "U1") (pin "41") (pinfunction "PI4_41") (pintype "passive"))
    )
    (net (code "197") (name "unconnected-(U1A-PI6-Pad38)") (class "Default")
      (node (ref "U1") (pin "38") (pinfunction "PI6_38") (pintype "passive"))
    )
    (net (code "198") (name "unconnected-(U1A-PI7-Pad42)") (class "Default")
      (node (ref "U1") (pin "42") (pinfunction "PI7_42") (pintype "passive"))
    )
    (net (code "199") (name "unconnected-(U1A-PI9-Pad57)") (class "Default")
      (node (ref "U1") (pin "57") (pinfunction "PI9_57") (pintype "passive"))
    )
    (net (code "200") (name "unconnected-(U1A-PI10-Pad61)") (class "Default")
      (node (ref "U1") (pin "61") (pinfunction "PI10_61") (pintype "passive"))
    )
    (net (code "201") (name "unconnected-(U1A-PZ0-Pad62)") (class "Default")
      (node (ref "U1") (pin "62") (pinfunction "PZ0_62") (pintype "passive"))
    )
    (net (code "202") (name "unconnected-(U1A-PZ1-Pad63)") (class "Default")
      (node (ref "U1") (pin "63") (pinfunction "PZ1_63") (pintype "passive"))
    )
    (net (code "203") (name "unconnected-(U1A-PZ6-Pad76)") (class "Default")
      (node (ref "U1") (pin "76") (pinfunction "PZ6_76") (pintype "passive"))
    )
    (net (code "204") (name "unconnected-(U1A-PZ7-Pad75)") (class "Default")
      (node (ref "U1") (pin "75") (pinfunction "PZ7_75") (pintype "passive"))
    )
    (net (code "205") (name "unconnected-(U1B-OTG_VBUS-Pad130)") (class "Default")
      (node (ref "U1") (pin "130") (pinfunction "OTG_VBUS_130") (pintype "passive"))
    )
    (net (code "206") (name "unconnected-(U1C-NC-Pad155)") (class "Default")
      (node (ref "U1") (pin "155") (pinfunction "NC_155") (pintype "passive+no_connect"))
    )
    (net (code "207") (name "unconnected-(U1C-NC-Pad157)") (class "Default")
      (node (ref "U1") (pin "157") (pinfunction "NC_157") (pintype "passive+no_connect"))
    )
    (net (code "208") (name "unconnected-(U1C-VBAT-Pad160)") (class "Default")
      (node (ref "U1") (pin "160") (pinfunction "VBAT_160") (pintype "passive"))
    )
    (net (code "209") (name "unconnected-(U2-D2IN-Pad28)") (class "Default")
      (node (ref "U2") (pin "28") (pinfunction "D2IN_28") (pintype "passive"))
    )
    (net (code "210") (name "unconnected-(U2-D2IP-Pad27)") (class "Default")
      (node (ref "U2") (pin "27") (pinfunction "D2IP_27") (pintype "passive"))
    )
    (net (code "211") (name "unconnected-(U2-D3IN-Pad30)") (class "Default")
      (node (ref "U2") (pin "30") (pinfunction "D3IN_30") (pintype "passive"))
    )
    (net (code "212") (name "unconnected-(U2-D3IP-Pad29)") (class "Default")
      (node (ref "U2") (pin "29") (pinfunction "D3IP_29") (pintype "passive"))
    )
    (net (code "213") (name "unconnected-(U2-NC-Pad1)") (class "Default")
      (node (ref "U2") (pin "1") (pinfunction "NC_1") (pintype "passive+no_connect"))
    )
    (net (code "214") (name "unconnected-(U2-NC-Pad4)") (class "Default")
      (node (ref "U2") (pin "4") (pinfunction "NC_4") (pintype "passive+no_connect"))
    )
    (net (code "215") (name "unconnected-(U2-NC-Pad5)") (class "Default")
      (node (ref "U2") (pin "5") (pinfunction "NC_5") (pintype "passive+no_connect"))
    )
    (net (code "216") (name "unconnected-(U2-NC-Pad6)") (class "Default")
      (node (ref "U2") (pin "6") (pinfunction "NC_6") (pintype "passive+no_connect"))
    )
    (net (code "217") (name "unconnected-(U2-NC-Pad7)") (class "Default")
      (node (ref "U2") (pin "7") (pinfunction "NC_7") (pintype "passive+no_connect"))
    )
    (net (code "218") (name "unconnected-(U2-NC-Pad8)") (class "Default")
      (node (ref "U2") (pin "8") (pinfunction "NC_8") (pintype "passive+no_connect"))
    )
    (net (code "219") (name "unconnected-(U2-NC-Pad9)") (class "Default")
      (node (ref "U2") (pin "9") (pinfunction "NC_9") (pintype "passive+no_connect"))
    )
    (net (code "220") (name "unconnected-(U2-NC-Pad10)") (class "Default")
      (node (ref "U2") (pin "10") (pinfunction "NC_10") (pintype "passive+no_connect"))
    )
    (net (code "221") (name "unconnected-(U2-NC-Pad11)") (class "Default")
      (node (ref "U2") (pin "11") (pinfunction "NC_11") (pintype "passive+no_connect"))
    )
    (net (code "222") (name "unconnected-(U2-NC-Pad12)") (class "Default")
      (node (ref "U2") (pin "12") (pinfunction "NC_12") (pintype "passive+no_connect"))
    )
    (net (code "223") (name "unconnected-(U2-NC-Pad13)") (class "Default")
      (node (ref "U2") (pin "13") (pinfunction "NC_13") (pintype "passive+no_connect"))
    )
    (net (code "224") (name "unconnected-(U2-NC-Pad34)") (class "Default")
      (node (ref "U2") (pin "34") (pinfunction "NC_34") (pintype "passive+no_connect"))
    )
    (net (code "225") (name "unconnected-(U2-NC-Pad50)") (class "Default")
      (node (ref "U2") (pin "50") (pinfunction "NC_50") (pintype "passive+no_connect"))
    )
    (net (code "226") (name "unconnected-(U2-NC-Pad51)") (class "Default")
      (node (ref "U2") (pin "51") (pinfunction "NC_51") (pintype "passive+no_connect"))
    )
    (net (code "227") (name "unconnected-(U2-NC-Pad53)") (class "Default")
      (node (ref "U2") (pin "53") (pinfunction "NC_53") (pintype "passive+no_connect"))
    )
    (net (code "228") (name "unconnected-(U2-NC-Pad54)") (class "Default")
      (node (ref "U2") (pin "54") (pinfunction "NC_54") (pintype "passive+no_connect"))
    )
    (net (code "229") (name "unconnected-(U2-NC-Pad56)") (class "Default")
      (node (ref "U2") (pin "56") (pinfunction "NC_56") (pintype "passive+no_connect"))
    )
    (net (code "230") (name "unconnected-(U2-NC-Pad57)") (class "Default")
      (node (ref "U2") (pin "57") (pinfunction "NC_57") (pintype "passive+no_connect"))
    )
    (net (code "231") (name "unconnected-(U2-NC-Pad59)") (class "Default")
      (node (ref "U2") (pin "59") (pinfunction "NC_59") (pintype "passive+no_connect"))
    )
    (net (code "232") (name "unconnected-(U2-NC-Pad60)") (class "Default")
      (node (ref "U2") (pin "60") (pinfunction "NC_60") (pintype "passive+no_connect"))
    )
    (net (code "233") (name "unconnected-(U2-NC-Pad61)") (class "Default")
      (node (ref "U2") (pin "61") (pinfunction "NC_61") (pintype "passive+no_connect"))
    )
    (net (code "234") (name "unconnected-(U2-NC-Pad62)") (class "Default")
      (node (ref "U2") (pin "62") (pinfunction "NC_62") (pintype "passive+no_connect"))
    )
    (net (code "235") (name "unconnected-(U4-LBK-Pad5)") (class "Default")
      (node (ref "U4") (pin "5") (pinfunction "LBK_5") (pintype "input+no_connect"))
    )
    (net (code "236") (name "unconnected-(U4-RS-Pad8)") (class "Default")
      (node (ref "U4") (pin "8") (pinfunction "RS_8") (pintype "input+no_connect"))
    )
    (net (code "237") (name "unconnected-(U7-OUT-Pad2)") (class "Default")
      (node (ref "U7") (pin "2") (pinfunction "OUT_2") (pintype "power_in"))
    )
    (net (code "238") (name "unconnected-(U10-LBK-Pad5)") (class "Default")
      (node (ref "U10") (pin "5") (pinfunction "LBK_5") (pintype "input+no_connect"))
    )
    (net (code "239") (name "unconnected-(U10-RS-Pad8)") (class "Default")
      (node (ref "U10") (pin "8") (pinfunction "RS_8") (pintype "input+no_connect"))
    )
  )
)
